# 15fpga.net
KiCad netlist of a schematic drawn in Altium Designer
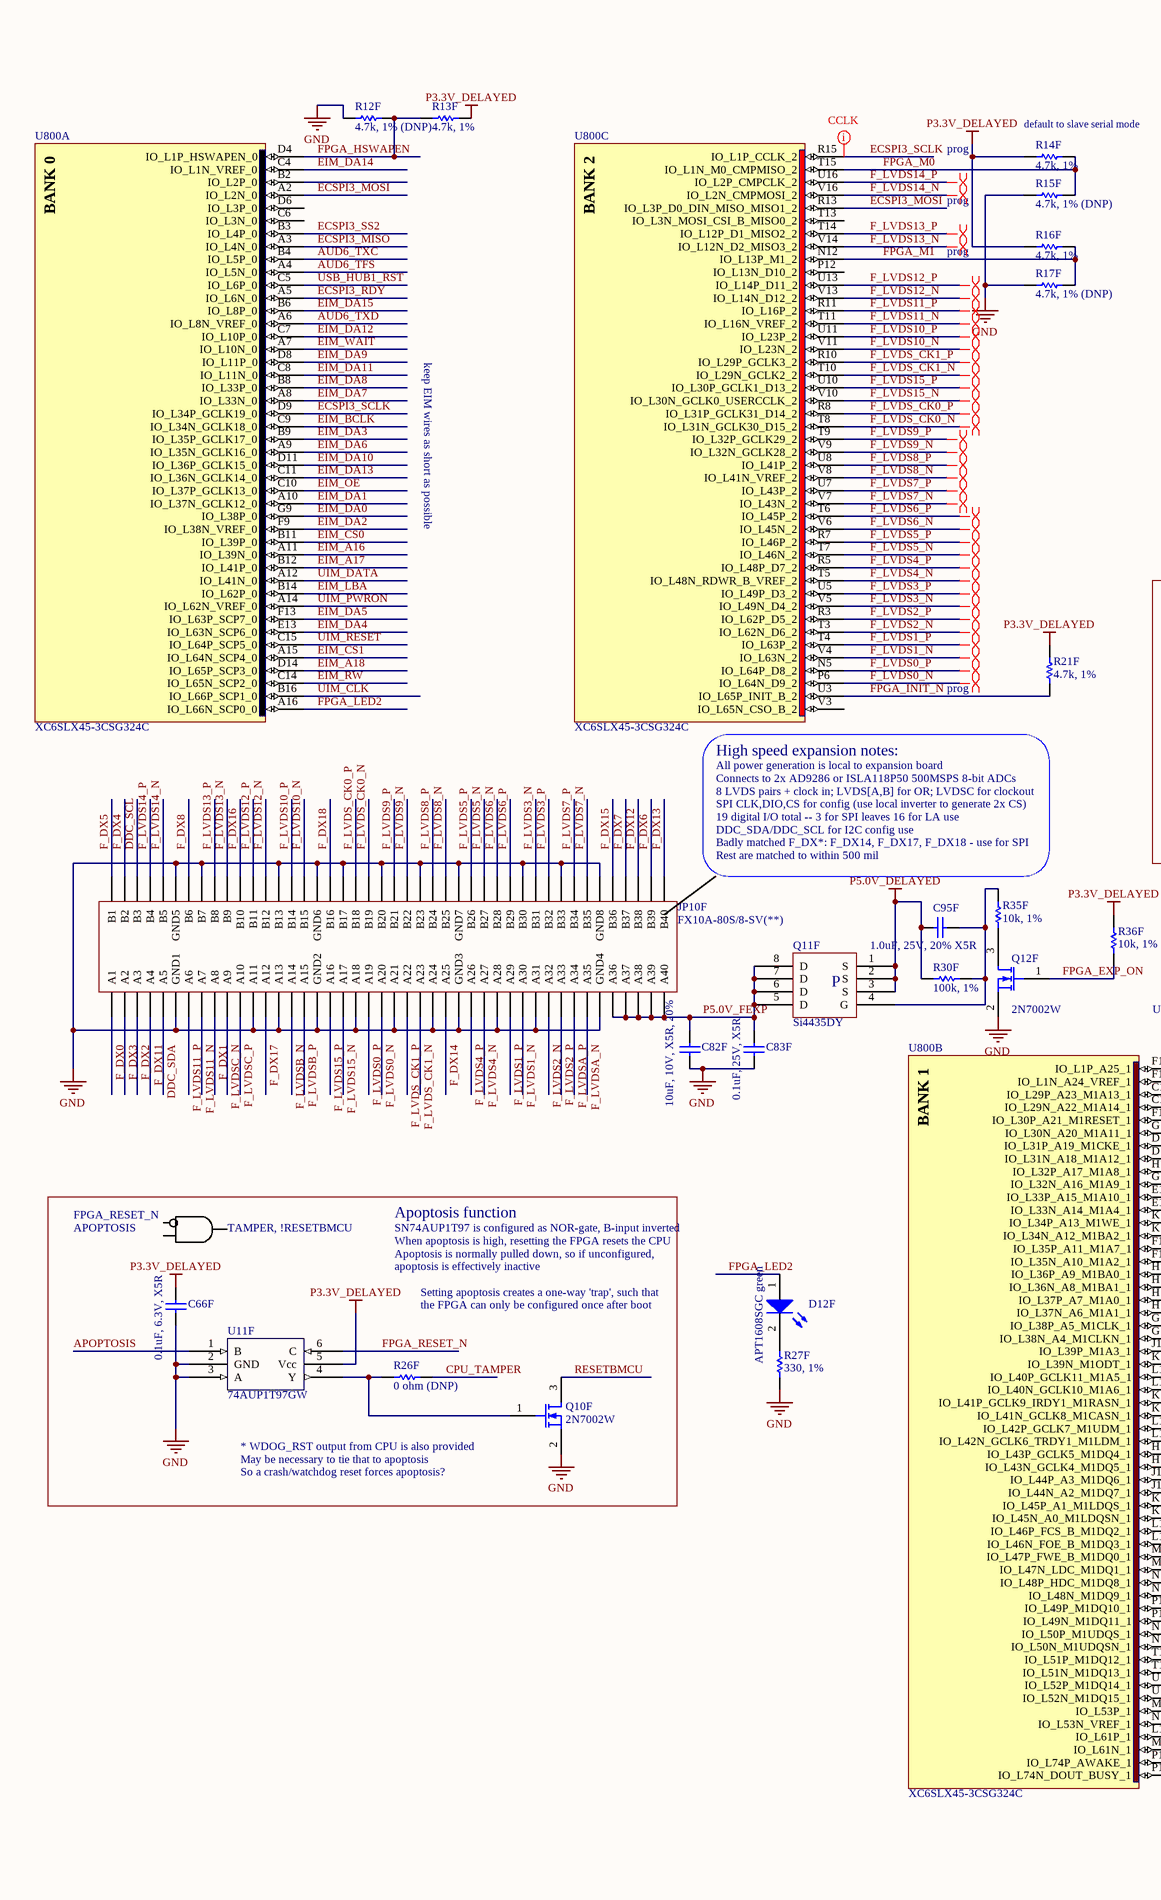
[diagram p0: 15fpga.SchDoc, left]
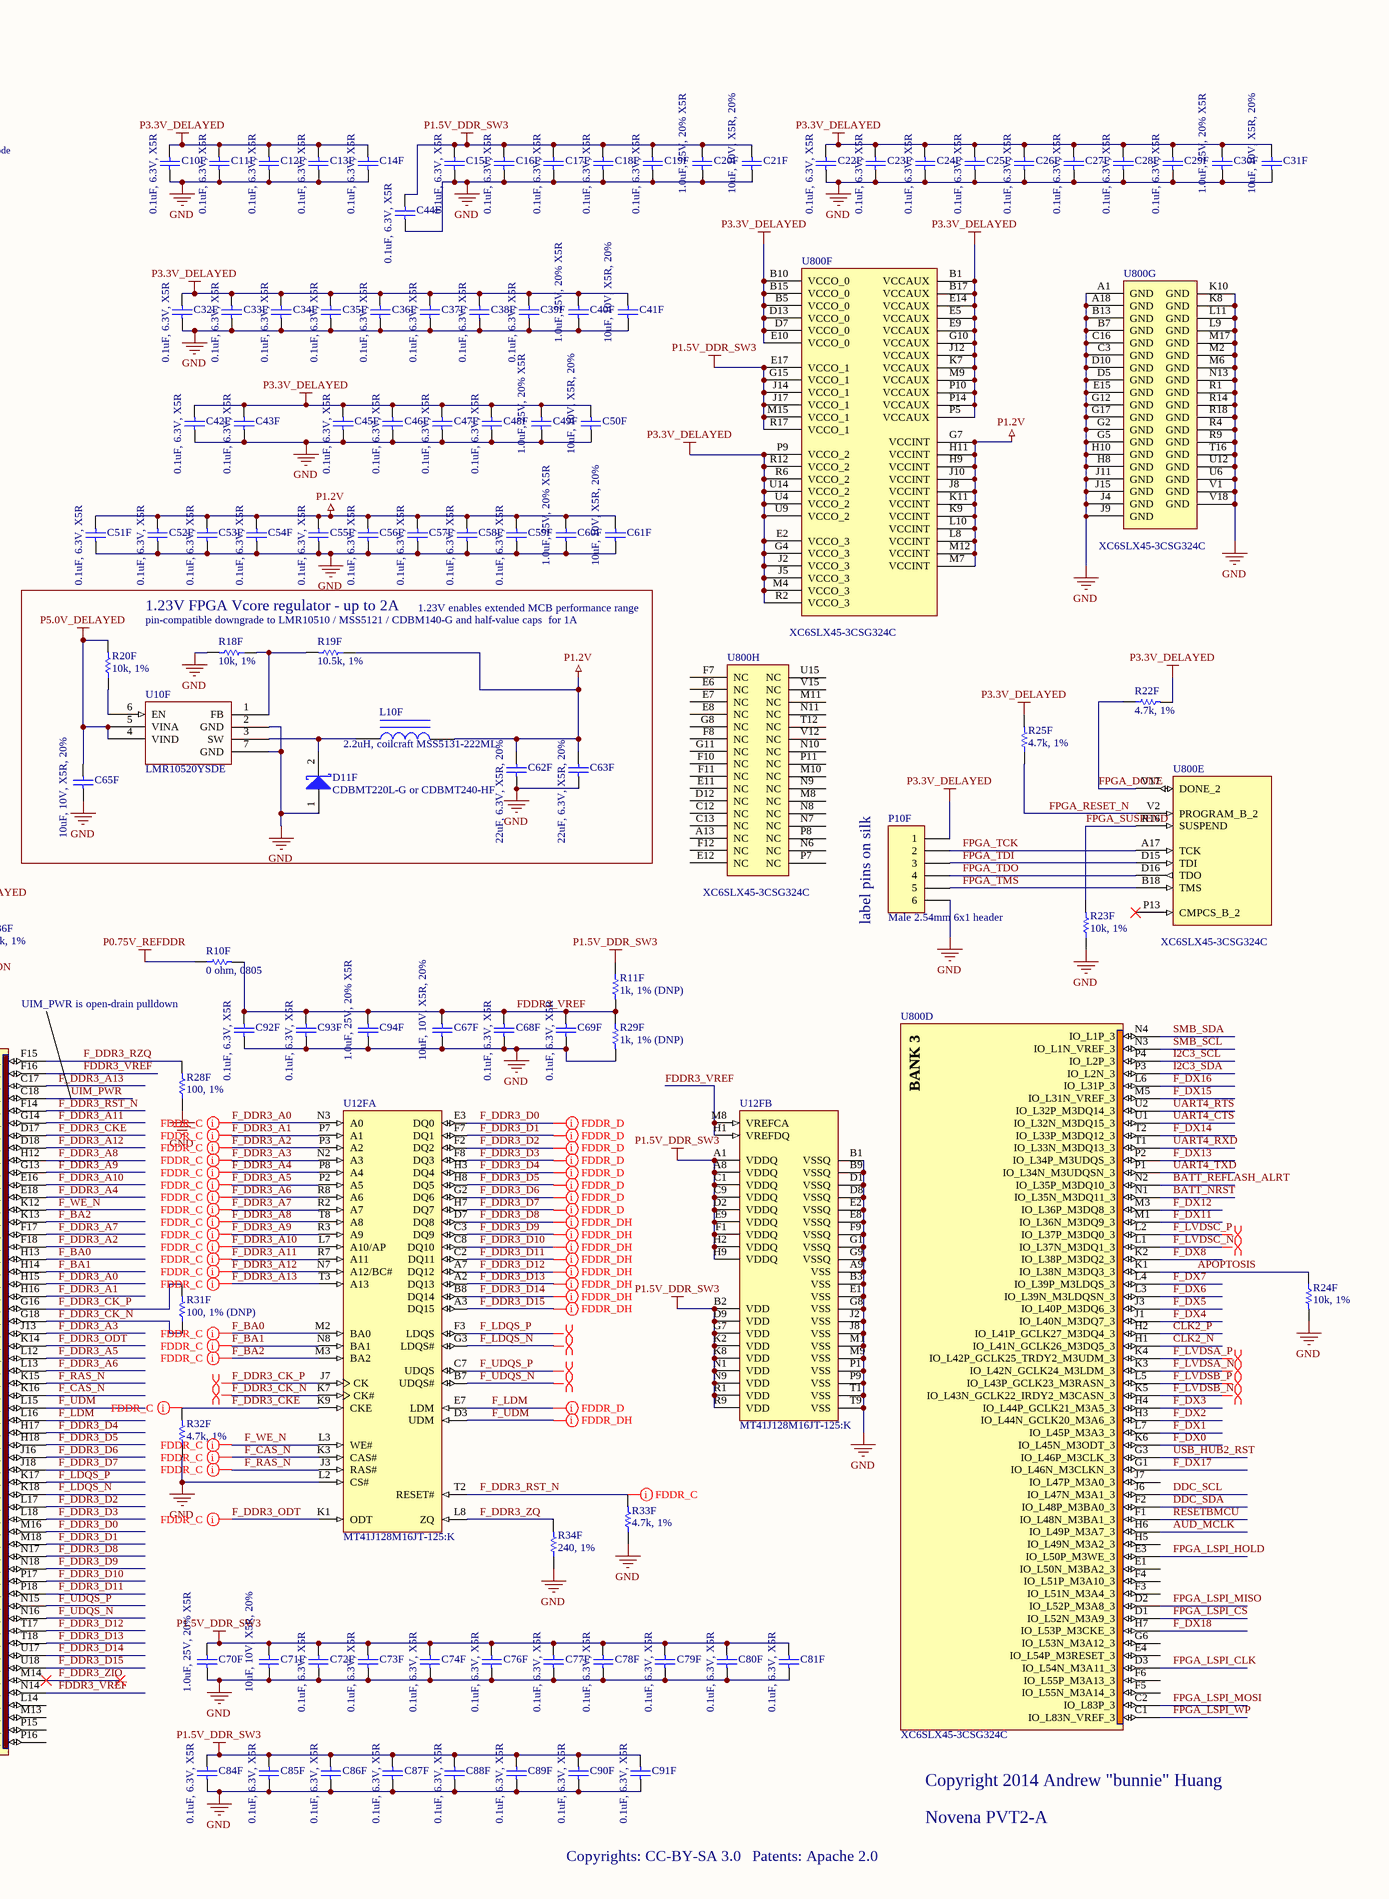
[diagram p1: 15fpga.SchDoc, right]

(export (version "E")
  (design (tool "Eeschema 10.0.6"))
  (components
    (comp (ref "C10F")
      (value "0.1uF, 6.3V, X5R")
      (footprint "CAPC0603N_B")
      (description "Capacitor (Semiconductor SIM Model)")
      (fields (field (name "PUBLISHER") "Altium Limited"))
      (libsource (lib "Miscellaneous Devices") (part "Cap Semi"))
    )
    (comp (ref "C11F")
      (value "0.1uF, 6.3V, X5R")
      (footprint "CAPC0603N_B")
      (description "Capacitor (Semiconductor SIM Model)")
      (fields (field (name "PUBLISHER") "Altium Limited"))
      (libsource (lib "Miscellaneous Devices") (part "Cap Semi"))
    )
    (comp (ref "C12F")
      (value "0.1uF, 6.3V, X5R")
      (footprint "CAPC0603N_B")
      (description "Capacitor (Semiconductor SIM Model)")
      (fields (field (name "PUBLISHER") "Altium Limited"))
      (libsource (lib "Miscellaneous Devices") (part "Cap Semi"))
    )
    (comp (ref "C13F")
      (value "0.1uF, 6.3V, X5R")
      (footprint "CAPC0603N_B")
      (description "Capacitor (Semiconductor SIM Model)")
      (fields (field (name "PUBLISHER") "Altium Limited"))
      (libsource (lib "Miscellaneous Devices") (part "Cap Semi"))
    )
    (comp (ref "C14F")
      (value "0.1uF, 6.3V, X5R")
      (footprint "CAPC0603N_B")
      (description "Capacitor (Semiconductor SIM Model)")
      (fields (field (name "PUBLISHER") "Altium Limited"))
      (libsource (lib "Miscellaneous Devices") (part "Cap Semi"))
    )
    (comp (ref "C15F")
      (value "0.1uF, 6.3V, X5R")
      (footprint "CAPC0603N_B")
      (description "Capacitor (Semiconductor SIM Model)")
      (fields (field (name "PUBLISHER") "Altium Limited"))
      (libsource (lib "Miscellaneous Devices") (part "Cap Semi"))
    )
    (comp (ref "C16F")
      (value "0.1uF, 6.3V, X5R")
      (footprint "CAPC0603N_B")
      (description "Capacitor (Semiconductor SIM Model)")
      (fields (field (name "PUBLISHER") "Altium Limited"))
      (libsource (lib "Miscellaneous Devices") (part "Cap Semi"))
    )
    (comp (ref "C17F")
      (value "0.1uF, 6.3V, X5R")
      (footprint "CAPC0603N_B")
      (description "Capacitor (Semiconductor SIM Model)")
      (fields (field (name "PUBLISHER") "Altium Limited"))
      (libsource (lib "Miscellaneous Devices") (part "Cap Semi"))
    )
    (comp (ref "C18F")
      (value "0.1uF, 6.3V, X5R")
      (footprint "CAPC0603N_B")
      (description "Capacitor (Semiconductor SIM Model)")
      (fields (field (name "PUBLISHER") "Altium Limited"))
      (libsource (lib "Miscellaneous Devices") (part "Cap Semi"))
    )
    (comp (ref "C19F")
      (value "0.1uF, 6.3V, X5R")
      (footprint "CAPC0603N_B")
      (description "Capacitor (Semiconductor SIM Model)")
      (fields (field (name "PUBLISHER") "Altium Limited"))
      (libsource (lib "Miscellaneous Devices") (part "Cap Semi"))
    )
    (comp (ref "C20F")
      (value "1.0uF, 25V, 20% X5R")
      (footprint "CAPC1608N")
      (description "Capacitor (Semiconductor SIM Model)")
      (fields (field (name "PUBLISHER") "Altium Limited"))
      (libsource (lib "Miscellaneous Devices") (part "Cap Semi"))
    )
    (comp (ref "C21F")
      (value "10uF, 10V, X5R, 20%")
      (footprint "CAPC1608N")
      (description "Capacitor (Semiconductor SIM Model)")
      (fields (field (name "PUBLISHER") "Altium Limited"))
      (libsource (lib "Miscellaneous Devices") (part "Cap Semi"))
    )
    (comp (ref "C22F")
      (value "0.1uF, 6.3V, X5R")
      (footprint "CAPC0603N_B")
      (description "Capacitor (Semiconductor SIM Model)")
      (fields (field (name "PUBLISHER") "Altium Limited"))
      (libsource (lib "Miscellaneous Devices") (part "Cap Semi"))
    )
    (comp (ref "C23F")
      (value "0.1uF, 6.3V, X5R")
      (footprint "CAPC0603N_B")
      (description "Capacitor (Semiconductor SIM Model)")
      (fields (field (name "PUBLISHER") "Altium Limited"))
      (libsource (lib "Miscellaneous Devices") (part "Cap Semi"))
    )
    (comp (ref "C24F")
      (value "0.1uF, 6.3V, X5R")
      (footprint "CAPC0603N_B")
      (description "Capacitor (Semiconductor SIM Model)")
      (fields (field (name "PUBLISHER") "Altium Limited"))
      (libsource (lib "Miscellaneous Devices") (part "Cap Semi"))
    )
    (comp (ref "C25F")
      (value "0.1uF, 6.3V, X5R")
      (footprint "CAPC0603N_B")
      (description "Capacitor (Semiconductor SIM Model)")
      (fields (field (name "PUBLISHER") "Altium Limited"))
      (libsource (lib "Miscellaneous Devices") (part "Cap Semi"))
    )
    (comp (ref "C26F")
      (value "0.1uF, 6.3V, X5R")
      (footprint "CAPC0603N_B")
      (description "Capacitor (Semiconductor SIM Model)")
      (fields (field (name "PUBLISHER") "Altium Limited"))
      (libsource (lib "Miscellaneous Devices") (part "Cap Semi"))
    )
    (comp (ref "C27F")
      (value "0.1uF, 6.3V, X5R")
      (footprint "CAPC0603N_B")
      (description "Capacitor (Semiconductor SIM Model)")
      (fields (field (name "PUBLISHER") "Altium Limited"))
      (libsource (lib "Miscellaneous Devices") (part "Cap Semi"))
    )
    (comp (ref "C28F")
      (value "0.1uF, 6.3V, X5R")
      (footprint "CAPC0603N_B")
      (description "Capacitor (Semiconductor SIM Model)")
      (fields (field (name "PUBLISHER") "Altium Limited"))
      (libsource (lib "Miscellaneous Devices") (part "Cap Semi"))
    )
    (comp (ref "C29F")
      (value "0.1uF, 6.3V, X5R")
      (footprint "CAPC0603N_B")
      (description "Capacitor (Semiconductor SIM Model)")
      (fields (field (name "PUBLISHER") "Altium Limited"))
      (libsource (lib "Miscellaneous Devices") (part "Cap Semi"))
    )
    (comp (ref "C30F")
      (value "1.0uF, 25V, 20% X5R")
      (footprint "CAPC1608N")
      (description "Capacitor (Semiconductor SIM Model)")
      (fields (field (name "PUBLISHER") "Altium Limited"))
      (libsource (lib "Miscellaneous Devices") (part "Cap Semi"))
    )
    (comp (ref "C31F")
      (value "10uF, 10V, X5R, 20%")
      (footprint "CAPC1608N")
      (description "Capacitor (Semiconductor SIM Model)")
      (fields (field (name "PUBLISHER") "Altium Limited"))
      (libsource (lib "Miscellaneous Devices") (part "Cap Semi"))
    )
    (comp (ref "C32F")
      (value "0.1uF, 6.3V, X5R")
      (footprint "CAPC0603N_B")
      (description "Capacitor (Semiconductor SIM Model)")
      (fields (field (name "PUBLISHER") "Altium Limited"))
      (libsource (lib "Miscellaneous Devices") (part "Cap Semi"))
    )
    (comp (ref "C33F")
      (value "0.1uF, 6.3V, X5R")
      (footprint "CAPC0603N_B")
      (description "Capacitor (Semiconductor SIM Model)")
      (fields (field (name "PUBLISHER") "Altium Limited"))
      (libsource (lib "Miscellaneous Devices") (part "Cap Semi"))
    )
    (comp (ref "C34F")
      (value "0.1uF, 6.3V, X5R")
      (footprint "CAPC0603N_B")
      (description "Capacitor (Semiconductor SIM Model)")
      (fields (field (name "PUBLISHER") "Altium Limited"))
      (libsource (lib "Miscellaneous Devices") (part "Cap Semi"))
    )
    (comp (ref "C35F")
      (value "0.1uF, 6.3V, X5R")
      (footprint "CAPC0603N_B")
      (description "Capacitor (Semiconductor SIM Model)")
      (fields (field (name "PUBLISHER") "Altium Limited"))
      (libsource (lib "Miscellaneous Devices") (part "Cap Semi"))
    )
    (comp (ref "C36F")
      (value "0.1uF, 6.3V, X5R")
      (footprint "CAPC0603N_B")
      (description "Capacitor (Semiconductor SIM Model)")
      (fields (field (name "PUBLISHER") "Altium Limited"))
      (libsource (lib "Miscellaneous Devices") (part "Cap Semi"))
    )
    (comp (ref "C37F")
      (value "0.1uF, 6.3V, X5R")
      (footprint "CAPC0603N_B")
      (description "Capacitor (Semiconductor SIM Model)")
      (fields (field (name "PUBLISHER") "Altium Limited"))
      (libsource (lib "Miscellaneous Devices") (part "Cap Semi"))
    )
    (comp (ref "C38F")
      (value "0.1uF, 6.3V, X5R")
      (footprint "CAPC0603N_B")
      (description "Capacitor (Semiconductor SIM Model)")
      (fields (field (name "PUBLISHER") "Altium Limited"))
      (libsource (lib "Miscellaneous Devices") (part "Cap Semi"))
    )
    (comp (ref "C39F")
      (value "0.1uF, 6.3V, X5R")
      (footprint "CAPC0603N_B")
      (description "Capacitor (Semiconductor SIM Model)")
      (fields (field (name "PUBLISHER") "Altium Limited"))
      (libsource (lib "Miscellaneous Devices") (part "Cap Semi"))
    )
    (comp (ref "C40F")
      (value "1.0uF, 25V, 20% X5R")
      (footprint "CAPC1608N")
      (description "Capacitor (Semiconductor SIM Model)")
      (fields (field (name "PUBLISHER") "Altium Limited"))
      (libsource (lib "Miscellaneous Devices") (part "Cap Semi"))
    )
    (comp (ref "C41F")
      (value "10uF, 10V, X5R, 20%")
      (footprint "CAPC1608N")
      (description "Capacitor (Semiconductor SIM Model)")
      (fields (field (name "PUBLISHER") "Altium Limited"))
      (libsource (lib "Miscellaneous Devices") (part "Cap Semi"))
    )
    (comp (ref "C42F")
      (value "0.1uF, 6.3V, X5R")
      (footprint "CAPC0603N_B")
      (description "Capacitor (Semiconductor SIM Model)")
      (fields (field (name "PUBLISHER") "Altium Limited"))
      (libsource (lib "Miscellaneous Devices") (part "Cap Semi"))
    )
    (comp (ref "C43F")
      (value "0.1uF, 6.3V, X5R")
      (footprint "CAPC0603N_B")
      (description "Capacitor (Semiconductor SIM Model)")
      (fields (field (name "PUBLISHER") "Altium Limited"))
      (libsource (lib "Miscellaneous Devices") (part "Cap Semi"))
    )
    (comp (ref "C44F")
      (value "0.1uF, 6.3V, X5R")
      (footprint "CAPC0603N_B")
      (description "Capacitor (Semiconductor SIM Model)")
      (fields (field (name "PUBLISHER") "Altium Limited"))
      (libsource (lib "Miscellaneous Devices") (part "Cap Semi"))
    )
    (comp (ref "C45F")
      (value "0.1uF, 6.3V, X5R")
      (footprint "CAPC0603N_B")
      (description "Capacitor (Semiconductor SIM Model)")
      (fields (field (name "PUBLISHER") "Altium Limited"))
      (libsource (lib "Miscellaneous Devices") (part "Cap Semi"))
    )
    (comp (ref "C46F")
      (value "0.1uF, 6.3V, X5R")
      (footprint "CAPC0603N_B")
      (description "Capacitor (Semiconductor SIM Model)")
      (fields (field (name "PUBLISHER") "Altium Limited"))
      (libsource (lib "Miscellaneous Devices") (part "Cap Semi"))
    )
    (comp (ref "C47F")
      (value "0.1uF, 6.3V, X5R")
      (footprint "CAPC0603N_B")
      (description "Capacitor (Semiconductor SIM Model)")
      (fields (field (name "PUBLISHER") "Altium Limited"))
      (libsource (lib "Miscellaneous Devices") (part "Cap Semi"))
    )
    (comp (ref "C48F")
      (value "0.1uF, 6.3V, X5R")
      (footprint "CAPC0603N_B")
      (description "Capacitor (Semiconductor SIM Model)")
      (fields (field (name "PUBLISHER") "Altium Limited"))
      (libsource (lib "Miscellaneous Devices") (part "Cap Semi"))
    )
    (comp (ref "C49F")
      (value "1.0uF, 25V, 20% X5R")
      (footprint "CAPC1608N")
      (description "Capacitor (Semiconductor SIM Model)")
      (fields (field (name "PUBLISHER") "Altium Limited"))
      (libsource (lib "Miscellaneous Devices") (part "Cap Semi"))
    )
    (comp (ref "C50F")
      (value "10uF, 10V, X5R, 20%")
      (footprint "CAPC1608N")
      (description "Capacitor (Semiconductor SIM Model)")
      (fields (field (name "PUBLISHER") "Altium Limited"))
      (libsource (lib "Miscellaneous Devices") (part "Cap Semi"))
    )
    (comp (ref "C51F")
      (value "0.1uF, 6.3V, X5R")
      (footprint "CAPC0603N_B")
      (description "Capacitor (Semiconductor SIM Model)")
      (fields (field (name "PUBLISHER") "Altium Limited"))
      (libsource (lib "Miscellaneous Devices") (part "Cap Semi"))
    )
    (comp (ref "C52F")
      (value "0.1uF, 6.3V, X5R")
      (footprint "CAPC0603N_B")
      (description "Capacitor (Semiconductor SIM Model)")
      (fields (field (name "PUBLISHER") "Altium Limited"))
      (libsource (lib "Miscellaneous Devices") (part "Cap Semi"))
    )
    (comp (ref "C53F")
      (value "0.1uF, 6.3V, X5R")
      (footprint "CAPC0603N_B")
      (description "Capacitor (Semiconductor SIM Model)")
      (fields (field (name "PUBLISHER") "Altium Limited"))
      (libsource (lib "Miscellaneous Devices") (part "Cap Semi"))
    )
    (comp (ref "C54F")
      (value "0.1uF, 6.3V, X5R")
      (footprint "CAPC0603N_B")
      (description "Capacitor (Semiconductor SIM Model)")
      (fields (field (name "PUBLISHER") "Altium Limited"))
      (libsource (lib "Miscellaneous Devices") (part "Cap Semi"))
    )
    (comp (ref "C55F")
      (value "0.1uF, 6.3V, X5R")
      (footprint "CAPC0603N_B")
      (description "Capacitor (Semiconductor SIM Model)")
      (fields (field (name "PUBLISHER") "Altium Limited"))
      (libsource (lib "Miscellaneous Devices") (part "Cap Semi"))
    )
    (comp (ref "C56F")
      (value "0.1uF, 6.3V, X5R")
      (footprint "CAPC0603N_B")
      (description "Capacitor (Semiconductor SIM Model)")
      (fields (field (name "PUBLISHER") "Altium Limited"))
      (libsource (lib "Miscellaneous Devices") (part "Cap Semi"))
    )
    (comp (ref "C57F")
      (value "0.1uF, 6.3V, X5R")
      (footprint "CAPC0603N_B")
      (description "Capacitor (Semiconductor SIM Model)")
      (fields (field (name "PUBLISHER") "Altium Limited"))
      (libsource (lib "Miscellaneous Devices") (part "Cap Semi"))
    )
    (comp (ref "C58F")
      (value "0.1uF, 6.3V, X5R")
      (footprint "CAPC0603N_B")
      (description "Capacitor (Semiconductor SIM Model)")
      (fields (field (name "PUBLISHER") "Altium Limited"))
      (libsource (lib "Miscellaneous Devices") (part "Cap Semi"))
    )
    (comp (ref "C59F")
      (value "0.1uF, 6.3V, X5R")
      (footprint "CAPC0603N_B")
      (description "Capacitor (Semiconductor SIM Model)")
      (fields (field (name "PUBLISHER") "Altium Limited"))
      (libsource (lib "Miscellaneous Devices") (part "Cap Semi"))
    )
    (comp (ref "C60F")
      (value "1.0uF, 25V, 20% X5R")
      (footprint "CAPC1608N")
      (description "Capacitor (Semiconductor SIM Model)")
      (fields (field (name "PUBLISHER") "Altium Limited"))
      (libsource (lib "Miscellaneous Devices") (part "Cap Semi"))
    )
    (comp (ref "C61F")
      (value "10uF, 10V, X5R, 20%")
      (footprint "CAPC1608N")
      (description "Capacitor (Semiconductor SIM Model)")
      (fields (field (name "PUBLISHER") "Altium Limited"))
      (libsource (lib "Miscellaneous Devices") (part "Cap Semi"))
    )
    (comp (ref "C62F")
      (value "22uF, 6.3V, X5R, 20%")
      (footprint "CAPC1608N_HD")
      (description "Capacitor (Semiconductor SIM Model)")
      (fields (field (name "PUBLISHER") "Altium Limited"))
      (libsource (lib "Miscellaneous Devices") (part "Cap Semi"))
    )
    (comp (ref "C63F")
      (value "22uF, 6.3V, X5R, 20%")
      (footprint "CAPC1608N_HD")
      (description "Capacitor (Semiconductor SIM Model)")
      (fields (field (name "PUBLISHER") "Altium Limited"))
      (libsource (lib "Miscellaneous Devices") (part "Cap Semi"))
    )
    (comp (ref "C65F")
      (value "10uF, 10V, X5R, 20%")
      (footprint "CAPC1608N")
      (description "Capacitor (Semiconductor SIM Model)")
      (fields (field (name "PUBLISHER") "Altium Limited"))
      (libsource (lib "Miscellaneous Devices") (part "Cap Semi"))
    )
    (comp (ref "C66F")
      (value "0.1uF, 6.3V, X5R")
      (footprint "CAPC0603N_B")
      (description "Capacitor (Semiconductor SIM Model)")
      (fields (field (name "PUBLISHER") "Altium Limited"))
      (libsource (lib "Miscellaneous Devices") (part "Cap Semi"))
    )
    (comp (ref "C67F")
      (value "10uF, 10V, X5R, 20%")
      (footprint "CAPC1608N")
      (description "Capacitor (Semiconductor SIM Model)")
      (fields (field (name "PUBLISHER") "Altium Limited"))
      (libsource (lib "Miscellaneous Devices") (part "Cap Semi"))
    )
    (comp (ref "C68F")
      (value "0.1uF, 6.3V, X5R")
      (footprint "CAPC0603N_B")
      (description "Capacitor (Semiconductor SIM Model)")
      (fields (field (name "PUBLISHER") "Altium Limited"))
      (libsource (lib "Miscellaneous Devices") (part "Cap Semi"))
    )
    (comp (ref "C69F")
      (value "0.1uF, 6.3V, X5R")
      (footprint "CAPC0603N_B")
      (description "Capacitor (Semiconductor SIM Model)")
      (fields (field (name "PUBLISHER") "Altium Limited"))
      (libsource (lib "Miscellaneous Devices") (part "Cap Semi"))
    )
    (comp (ref "C70F")
      (value "1.0uF, 25V, 20% X5R")
      (footprint "CAPC1608N")
      (description "Capacitor (Semiconductor SIM Model)")
      (fields (field (name "PUBLISHER") "Altium Limited"))
      (libsource (lib "Miscellaneous Devices") (part "Cap Semi"))
    )
    (comp (ref "C71F")
      (value "10uF, 10V, X5R, 20%")
      (footprint "CAPC1608N")
      (description "Capacitor (Semiconductor SIM Model)")
      (fields (field (name "PUBLISHER") "Altium Limited"))
      (libsource (lib "Miscellaneous Devices") (part "Cap Semi"))
    )
    (comp (ref "C72F")
      (value "0.1uF, 6.3V, X5R")
      (footprint "CAPC0603N_B")
      (description "Capacitor (Semiconductor SIM Model)")
      (fields (field (name "PUBLISHER") "Altium Limited"))
      (libsource (lib "Miscellaneous Devices") (part "Cap Semi"))
    )
    (comp (ref "C73F")
      (value "0.1uF, 6.3V, X5R")
      (footprint "CAPC0603N_B")
      (description "Capacitor (Semiconductor SIM Model)")
      (fields (field (name "PUBLISHER") "Altium Limited"))
      (libsource (lib "Miscellaneous Devices") (part "Cap Semi"))
    )
    (comp (ref "C74F")
      (value "0.1uF, 6.3V, X5R")
      (footprint "CAPC0603N_B")
      (description "Capacitor (Semiconductor SIM Model)")
      (fields (field (name "PUBLISHER") "Altium Limited"))
      (libsource (lib "Miscellaneous Devices") (part "Cap Semi"))
    )
    (comp (ref "C76F")
      (value "0.1uF, 6.3V, X5R")
      (footprint "CAPC0603N_B")
      (description "Capacitor (Semiconductor SIM Model)")
      (fields (field (name "PUBLISHER") "Altium Limited"))
      (libsource (lib "Miscellaneous Devices") (part "Cap Semi"))
    )
    (comp (ref "C77F")
      (value "0.1uF, 6.3V, X5R")
      (footprint "CAPC0603N_B")
      (description "Capacitor (Semiconductor SIM Model)")
      (fields (field (name "PUBLISHER") "Altium Limited"))
      (libsource (lib "Miscellaneous Devices") (part "Cap Semi"))
    )
    (comp (ref "C78F")
      (value "0.1uF, 6.3V, X5R")
      (footprint "CAPC0603N_B")
      (description "Capacitor (Semiconductor SIM Model)")
      (fields (field (name "PUBLISHER") "Altium Limited"))
      (libsource (lib "Miscellaneous Devices") (part "Cap Semi"))
    )
    (comp (ref "C79F")
      (value "0.1uF, 6.3V, X5R")
      (footprint "CAPC0603N_B")
      (description "Capacitor (Semiconductor SIM Model)")
      (fields (field (name "PUBLISHER") "Altium Limited"))
      (libsource (lib "Miscellaneous Devices") (part "Cap Semi"))
    )
    (comp (ref "C80F")
      (value "0.1uF, 6.3V, X5R")
      (footprint "CAPC0603N_B")
      (description "Capacitor (Semiconductor SIM Model)")
      (fields (field (name "PUBLISHER") "Altium Limited"))
      (libsource (lib "Miscellaneous Devices") (part "Cap Semi"))
    )
    (comp (ref "C81F")
      (value "0.1uF, 6.3V, X5R")
      (footprint "CAPC0603N_B")
      (description "Capacitor (Semiconductor SIM Model)")
      (fields (field (name "PUBLISHER") "Altium Limited"))
      (libsource (lib "Miscellaneous Devices") (part "Cap Semi"))
    )
    (comp (ref "C82F")
      (value "10uF, 10V, X5R, 20%")
      (footprint "CAPC1608N")
      (description "Capacitor (Semiconductor SIM Model)")
      (fields (field (name "PUBLISHER") "Altium Limited"))
      (libsource (lib "Miscellaneous Devices") (part "Cap Semi"))
    )
    (comp (ref "C83F")
      (value "0.1uF, 25V, X5R")
      (footprint "CAPC1005N")
      (description "Capacitor (Semiconductor SIM Model)")
      (fields (field (name "PUBLISHER") "Altium Limited"))
      (libsource (lib "Miscellaneous Devices") (part "Cap Semi"))
    )
    (comp (ref "C84F")
      (value "0.1uF, 6.3V, X5R")
      (footprint "CAPC0603N_B")
      (description "Capacitor (Semiconductor SIM Model)")
      (fields (field (name "PUBLISHER") "Altium Limited"))
      (libsource (lib "Miscellaneous Devices") (part "Cap Semi"))
    )
    (comp (ref "C85F")
      (value "0.1uF, 6.3V, X5R")
      (footprint "CAPC0603N_B")
      (description "Capacitor (Semiconductor SIM Model)")
      (fields (field (name "PUBLISHER") "Altium Limited"))
      (libsource (lib "Miscellaneous Devices") (part "Cap Semi"))
    )
    (comp (ref "C86F")
      (value "0.1uF, 6.3V, X5R")
      (footprint "CAPC0603N_B")
      (description "Capacitor (Semiconductor SIM Model)")
      (fields (field (name "PUBLISHER") "Altium Limited"))
      (libsource (lib "Miscellaneous Devices") (part "Cap Semi"))
    )
    (comp (ref "C87F")
      (value "0.1uF, 6.3V, X5R")
      (footprint "CAPC0603N_B")
      (description "Capacitor (Semiconductor SIM Model)")
      (fields (field (name "PUBLISHER") "Altium Limited"))
      (libsource (lib "Miscellaneous Devices") (part "Cap Semi"))
    )
    (comp (ref "C88F")
      (value "0.1uF, 6.3V, X5R")
      (footprint "CAPC0603N_B")
      (description "Capacitor (Semiconductor SIM Model)")
      (fields (field (name "PUBLISHER") "Altium Limited"))
      (libsource (lib "Miscellaneous Devices") (part "Cap Semi"))
    )
    (comp (ref "C89F")
      (value "0.1uF, 6.3V, X5R")
      (footprint "CAPC0603N_B")
      (description "Capacitor (Semiconductor SIM Model)")
      (fields (field (name "PUBLISHER") "Altium Limited"))
      (libsource (lib "Miscellaneous Devices") (part "Cap Semi"))
    )
    (comp (ref "C90F")
      (value "0.1uF, 6.3V, X5R")
      (footprint "CAPC0603N_B")
      (description "Capacitor (Semiconductor SIM Model)")
      (fields (field (name "PUBLISHER") "Altium Limited"))
      (libsource (lib "Miscellaneous Devices") (part "Cap Semi"))
    )
    (comp (ref "C91F")
      (value "0.1uF, 6.3V, X5R")
      (footprint "CAPC0603N_B")
      (description "Capacitor (Semiconductor SIM Model)")
      (fields (field (name "PUBLISHER") "Altium Limited"))
      (libsource (lib "Miscellaneous Devices") (part "Cap Semi"))
    )
    (comp (ref "C92F")
      (value "0.1uF, 6.3V, X5R")
      (footprint "CAPC0603N_B")
      (description "Capacitor (Semiconductor SIM Model)")
      (fields (field (name "PUBLISHER") "Altium Limited"))
      (libsource (lib "Miscellaneous Devices") (part "Cap Semi"))
    )
    (comp (ref "C93F")
      (value "0.1uF, 6.3V, X5R")
      (footprint "CAPC0603N_B")
      (description "Capacitor (Semiconductor SIM Model)")
      (fields (field (name "PUBLISHER") "Altium Limited"))
      (libsource (lib "Miscellaneous Devices") (part "Cap Semi"))
    )
    (comp (ref "C94F")
      (value "1.0uF, 25V, 20% X5R")
      (footprint "CAPC1608N")
      (description "Capacitor (Semiconductor SIM Model)")
      (fields (field (name "PUBLISHER") "Altium Limited"))
      (libsource (lib "Miscellaneous Devices") (part "Cap Semi"))
    )
    (comp (ref "C95F")
      (value "1.0uF, 25V, 20% X5R")
      (footprint "CAPC1608N")
      (description "Capacitor (Semiconductor SIM Model)")
      (fields (field (name "PUBLISHER") "Altium Limited"))
      (libsource (lib "Miscellaneous Devices") (part "Cap Semi"))
    )
    (comp (ref "D11F")
      (value "CDBMT220L-G or CDBMT240-HF")
      (footprint "SOD123")
      (description "Schottky Diode")
      (fields (field (name "PUBLISHER") "Altium Limited"))
      (libsource (lib "Miscellaneous Devices") (part "D Schottky"))
    )
    (comp (ref "D12F")
      (value "APT1608SGC green")
      (footprint "CD1608-0603")
      (description "Typical RED, GREEN, YELLOW, AMBER GaAs LED")
      (fields (field (name "PUBLISHER") "Altium Limited"))
      (libsource (lib "Miscellaneous Devices") (part "LED2"))
    )
    (comp (ref "JP10F")
      (value "FX10A-80S/8-SV(**)")
      (footprint "HRS_FX10A-80S/8-SV1(**)")
      (description "80-pin 10Gbps 5mm mated height board-to-board connector")
      (libsource (lib "commonsch") (part "HEADER_HRS_FX10A_80"))
    )
    (comp (ref "L10F")
      (value "2.2uH, coilcraft MSS5131-222ML")
      (footprint "COILCRAFT_MSS5121")
      (description "Magnetic-Core Inductor")
      (fields (field (name "PUBLISHER") "Altium Limited"))
      (libsource (lib "Miscellaneous Devices") (part "Inductor Iron"))
    )
    (comp (ref "P10F")
      (value "Male 2.54mm 6x1 header")
      (footprint "HDR1X6")
      (description "Header, 6-Pin")
      (fields (field (name "PUBLISHER") "Altium Limited"))
      (libsource (lib "Miscellaneous Connectors") (part "Header 6"))
    )
    (comp (ref "Q10F")
      (value "2N7002W")
      (footprint "SOT323-3AN")
      (description "N-Channel MOSFET")
      (fields (field (name "PUBLISHER") "Altium Limited"))
      (libsource (lib "Miscellaneous Devices") (part "MOSFET-N"))
    )
    (comp (ref "Q11F")
      (value "Si4435DY")
      (footprint "SOIC127P600-8AN")
      (description "Singre P-channel FET, 8A, 30V")
      (libsource (lib "commonsch") (part "Si4435DY"))
    )
    (comp (ref "Q12F")
      (value "2N7002W")
      (footprint "SOT323-3AN")
      (description "N-Channel MOSFET")
      (fields (field (name "PUBLISHER") "Altium Limited"))
      (libsource (lib "Miscellaneous Devices") (part "MOSFET-N"))
    )
    (comp (ref "R10F")
      (value "0 ohm, 0805")
      (footprint "RESC2012N")
      (description "Resistor")
      (fields (field (name "PUBLISHER") "Altium Limited"))
      (libsource (lib "Miscellaneous Devices") (part "Res1"))
    )
    (comp (ref "R11F")
      (value "1k, 1% (DNP)")
      (footprint "RESC1005N")
      (description "Resistor")
      (fields (field (name "PUBLISHER") "Altium Limited"))
      (libsource (lib "Miscellaneous Devices") (part "Res1"))
    )
    (comp (ref "R12F")
      (value "4.7k, 1% (DNP)")
      (footprint "RESC1005N")
      (description "Resistor")
      (fields (field (name "PUBLISHER") "Altium Limited"))
      (libsource (lib "Miscellaneous Devices") (part "Res1"))
    )
    (comp (ref "R13F")
      (value "4.7k, 1%")
      (footprint "RESC1005N")
      (description "Resistor")
      (fields (field (name "PUBLISHER") "Altium Limited"))
      (libsource (lib "Miscellaneous Devices") (part "Res1"))
    )
    (comp (ref "R14F")
      (value "4.7k, 1%")
      (footprint "RESC1005N")
      (description "Resistor")
      (fields (field (name "PUBLISHER") "Altium Limited"))
      (libsource (lib "Miscellaneous Devices") (part "Res1"))
    )
    (comp (ref "R15F")
      (value "4.7k, 1% (DNP)")
      (footprint "RESC1005N")
      (description "Resistor")
      (fields (field (name "PUBLISHER") "Altium Limited"))
      (libsource (lib "Miscellaneous Devices") (part "Res1"))
    )
    (comp (ref "R16F")
      (value "4.7k, 1%")
      (footprint "RESC1005N")
      (description "Resistor")
      (fields (field (name "PUBLISHER") "Altium Limited"))
      (libsource (lib "Miscellaneous Devices") (part "Res1"))
    )
    (comp (ref "R17F")
      (value "4.7k, 1% (DNP)")
      (footprint "RESC1005N")
      (description "Resistor")
      (fields (field (name "PUBLISHER") "Altium Limited"))
      (libsource (lib "Miscellaneous Devices") (part "Res1"))
    )
    (comp (ref "R18F")
      (value "10k, 1%")
      (footprint "RESC1005N")
      (description "Resistor")
      (fields (field (name "PUBLISHER") "Altium Limited"))
      (libsource (lib "Miscellaneous Devices") (part "Res1"))
    )
    (comp (ref "R19F")
      (value "10.5k, 1%")
      (footprint "RESC1005N")
      (description "Resistor")
      (fields (field (name "PUBLISHER") "Altium Limited"))
      (libsource (lib "Miscellaneous Devices") (part "Res1"))
    )
    (comp (ref "R20F")
      (value "10k, 1%")
      (footprint "RESC1005N")
      (description "Resistor")
      (fields (field (name "PUBLISHER") "Altium Limited"))
      (libsource (lib "Miscellaneous Devices") (part "Res1"))
    )
    (comp (ref "R21F")
      (value "4.7k, 1%")
      (footprint "RESC1005N")
      (description "Resistor")
      (fields (field (name "PUBLISHER") "Altium Limited"))
      (libsource (lib "Miscellaneous Devices") (part "Res1"))
    )
    (comp (ref "R22F")
      (value "4.7k, 1%")
      (footprint "RESC1005N")
      (description "Resistor")
      (fields (field (name "PUBLISHER") "Altium Limited"))
      (libsource (lib "Miscellaneous Devices") (part "Res1"))
    )
    (comp (ref "R23F")
      (value "10k, 1%")
      (footprint "RESC1005N")
      (description "Resistor")
      (fields (field (name "PUBLISHER") "Altium Limited"))
      (libsource (lib "Miscellaneous Devices") (part "Res1"))
    )
    (comp (ref "R24F")
      (value "10k, 1%")
      (footprint "RESC1005N")
      (description "Resistor")
      (fields (field (name "PUBLISHER") "Altium Limited"))
      (libsource (lib "Miscellaneous Devices") (part "Res1"))
    )
    (comp (ref "R25F")
      (value "4.7k, 1%")
      (footprint "RESC1005N")
      (description "Resistor")
      (fields (field (name "PUBLISHER") "Altium Limited"))
      (libsource (lib "Miscellaneous Devices") (part "Res1"))
    )
    (comp (ref "R26F")
      (value "0 ohm (DNP)")
      (footprint "RESC1005N")
      (description "Resistor")
      (fields (field (name "PUBLISHER") "Altium Limited"))
      (libsource (lib "Miscellaneous Devices") (part "Res1"))
    )
    (comp (ref "R27F")
      (value "330, 1%")
      (footprint "RESC1005N")
      (description "Resistor")
      (fields (field (name "PUBLISHER") "Altium Limited"))
      (libsource (lib "Miscellaneous Devices") (part "Res1"))
    )
    (comp (ref "R28F")
      (value "100, 1%")
      (footprint "RESC1005N")
      (description "Resistor")
      (fields (field (name "PUBLISHER") "Altium Limited"))
      (libsource (lib "Miscellaneous Devices") (part "Res1"))
    )
    (comp (ref "R29F")
      (value "1k, 1% (DNP)")
      (footprint "RESC1005N")
      (description "Resistor")
      (fields (field (name "PUBLISHER") "Altium Limited"))
      (libsource (lib "Miscellaneous Devices") (part "Res1"))
    )
    (comp (ref "R30F")
      (value "100k, 1%")
      (footprint "RESC1005N")
      (description "Resistor")
      (fields (field (name "PUBLISHER") "Altium Limited"))
      (libsource (lib "Miscellaneous Devices") (part "Res1"))
    )
    (comp (ref "R31F")
      (value "100, 1% (DNP)")
      (footprint "RESC1005N")
      (description "Resistor")
      (fields (field (name "PUBLISHER") "Altium Limited"))
      (libsource (lib "Miscellaneous Devices") (part "Res1"))
    )
    (comp (ref "R32F")
      (value "4.7k, 1%")
      (footprint "RESC1005N")
      (description "Resistor")
      (fields (field (name "PUBLISHER") "Altium Limited"))
      (libsource (lib "Miscellaneous Devices") (part "Res1"))
    )
    (comp (ref "R33F")
      (value "4.7k, 1%")
      (footprint "RESC1005N")
      (description "Resistor")
      (fields (field (name "PUBLISHER") "Altium Limited"))
      (libsource (lib "Miscellaneous Devices") (part "Res1"))
    )
    (comp (ref "R34F")
      (value "240, 1%")
      (footprint "RESC1005N")
      (description "Resistor")
      (fields (field (name "PUBLISHER") "Altium Limited"))
      (libsource (lib "Miscellaneous Devices") (part "Res1"))
    )
    (comp (ref "R35F")
      (value "10k, 1%")
      (footprint "RESC1005N")
      (description "Resistor")
      (fields (field (name "PUBLISHER") "Altium Limited"))
      (libsource (lib "Miscellaneous Devices") (part "Res1"))
    )
    (comp (ref "R36F")
      (value "10k, 1%")
      (footprint "RESC1005N")
      (description "Resistor")
      (fields (field (name "PUBLISHER") "Altium Limited"))
      (libsource (lib "Miscellaneous Devices") (part "Res1"))
    )
    (comp (ref "U10F")
      (value "LMR10520YSDE")
      (footprint "SON95P300X300X80-7V")
      (description "NatSemi 1.5A step-down regulator in LLP")
      (libsource (lib "commonsch") (part "LMR10515XSD"))
    )
    (comp (ref "U11F")
      (value "74AUP1T97GW")
      (footprint "SOT363-6N")
      (description "Single-supply voltage translator, multiple logic function")
      (libsource (lib "*") (part "SN74AUP1T98DBV"))
    )
    (comp (ref "U12F")
      (value "MT41J128M16JT-125:K")
      (footprint "MICT-HA-96")
      (description "2Gb DDR3-1600 SDRAM, 128Mb x 16, 1.25ns, 1.5V, 0 to 95 degC, 96-Ball FBGA, Pb-Free")
      (fields (field (name "VOLTAGE") "1.5V ") (field (name "MANUFACTURER") "Micron"))
      (libsource (lib "Micron Memory DDR3 SDRAM") (part "MT41J128M16HA-125"))
    )
    (comp (ref "U800")
      (value "XC6SLX45-3CSG324C")
      (footprint "CSG324")
      (fields (field (name "PUBLISHER") "Altium Limited"))
      (libsource (lib "Xilinx Spartan-6") (part "XC6SLX9-2CSG324C"))
    )
  )
  (nets
    (net (code "1") (name "/APOPTOSIS") (class "Default")
      (node (ref "R24F") (pin "1") (pinfunction "1_1") (pintype "passive"))
      (node (ref "U11F") (pin "1") (pinfunction "B_1") (pintype "input"))
      (node (ref "U800") (pin "K1") (pinfunction "IO_L38N_M3DQ3_3_K1") (pintype "bidirectional"))
    )
    (net (code "2") (name "/AUD6_TFS") (class "Default")
      (node (ref "U800") (pin "A4") (pinfunction "IO_L5N_0_A4") (pintype "bidirectional"))
    )
    (net (code "3") (name "/AUD6_TXC") (class "Default")
      (node (ref "U800") (pin "B4") (pinfunction "IO_L5P_0_B4") (pintype "bidirectional"))
    )
    (net (code "4") (name "/AUD6_TXD") (class "Default")
      (node (ref "U800") (pin "A6") (pinfunction "IO_L8N_VREF_0_A6") (pintype "bidirectional"))
    )
    (net (code "5") (name "/AUD_MCLK") (class "Default")
      (node (ref "U800") (pin "H6") (pinfunction "IO_L49P_M3A7_3_H6") (pintype "bidirectional"))
    )
    (net (code "6") (name "/BATT_NRST") (class "Default")
      (node (ref "U800") (pin "N1") (pinfunction "IO_L35N_M3DQ11_3_N1") (pintype "bidirectional"))
    )
    (net (code "7") (name "/BATT_REFLASH_ALRT") (class "Default")
      (node (ref "U800") (pin "N2") (pinfunction "IO_L35P_M3DQ10_3_N2") (pintype "bidirectional"))
    )
    (net (code "8") (name "/CLK2_N") (class "Default")
      (node (ref "U800") (pin "H1") (pinfunction "IO_L41N_GCLK26_M3DQ5_3_H1") (pintype "bidirectional"))
    )
    (net (code "9") (name "/CLK2_P") (class "Default")
      (node (ref "U800") (pin "H2") (pinfunction "IO_L41P_GCLK27_M3DQ4_3_H2") (pintype "bidirectional"))
    )
    (net (code "10") (name "/CPU_TAMPER") (class "Default")
      (node (ref "R26F") (pin "2") (pinfunction "2_2") (pintype "passive"))
    )
    (net (code "11") (name "/DDC_SCL") (class "Default")
      (node (ref "JP10F") (pin "B3") (pinfunction "B3_B3") (pintype "passive"))
      (node (ref "U800") (pin "J6") (pinfunction "IO_L47N_M3A1_3_J6") (pintype "bidirectional"))
    )
    (net (code "12") (name "/DDC_SDA") (class "Default")
      (node (ref "JP10F") (pin "A5") (pinfunction "A5_A5") (pintype "passive"))
      (node (ref "U800") (pin "F2") (pinfunction "IO_L48P_M3BA0_3_F2") (pintype "bidirectional"))
    )
    (net (code "13") (name "/ECSPI3_MISO") (class "Default")
      (node (ref "U800") (pin "A3") (pinfunction "IO_L4N_0_A3") (pintype "bidirectional"))
    )
    (net (code "14") (name "/ECSPI3_MOSI") (class "Default")
      (node (ref "U800") (pin "A2") (pinfunction "IO_L2N_0_A2") (pintype "bidirectional"))
      (node (ref "U800") (pin "R13") (pinfunction "IO_L3P_D0_DIN_MISO_MISO1_2_R13") (pintype "bidirectional"))
    )
    (net (code "15") (name "/ECSPI3_RDY") (class "Default")
      (node (ref "U800") (pin "A5") (pinfunction "IO_L6N_0_A5") (pintype "bidirectional"))
    )
    (net (code "16") (name "/ECSPI3_SCLK") (class "Default")
      (node (ref "U800") (pin "D9") (pinfunction "IO_L34P_GCLK19_0_D9") (pintype "bidirectional"))
      (node (ref "U800") (pin "R15") (pinfunction "IO_L1P_CCLK_2_R15") (pintype "bidirectional"))
    )
    (net (code "17") (name "/ECSPI3_SS2") (class "Default")
      (node (ref "U800") (pin "B3") (pinfunction "IO_L4P_0_B3") (pintype "bidirectional"))
    )
    (net (code "18") (name "/EIM_A16") (class "Default")
      (node (ref "U800") (pin "A11") (pinfunction "IO_L39N_0_A11") (pintype "bidirectional"))
    )
    (net (code "19") (name "/EIM_A17") (class "Default")
      (node (ref "U800") (pin "B12") (pinfunction "IO_L41P_0_B12") (pintype "bidirectional"))
    )
    (net (code "20") (name "/EIM_A18") (class "Default")
      (node (ref "U800") (pin "D14") (pinfunction "IO_L65P_SCP3_0_D14") (pintype "bidirectional"))
    )
    (net (code "21") (name "/EIM_BCLK") (class "Default")
      (node (ref "U800") (pin "C9") (pinfunction "IO_L34N_GCLK18_0_C9") (pintype "bidirectional"))
    )
    (net (code "22") (name "/EIM_CS0") (class "Default")
      (node (ref "U800") (pin "B11") (pinfunction "IO_L39P_0_B11") (pintype "bidirectional"))
    )
    (net (code "23") (name "/EIM_CS1") (class "Default")
      (node (ref "U800") (pin "A15") (pinfunction "IO_L64N_SCP4_0_A15") (pintype "bidirectional"))
    )
    (net (code "24") (name "/EIM_DA0") (class "Default")
      (node (ref "U800") (pin "G9") (pinfunction "IO_L38P_0_G9") (pintype "bidirectional"))
    )
    (net (code "25") (name "/EIM_DA1") (class "Default")
      (node (ref "U800") (pin "A10") (pinfunction "IO_L37N_GCLK12_0_A10") (pintype "bidirectional"))
    )
    (net (code "26") (name "/EIM_DA2") (class "Default")
      (node (ref "U800") (pin "F9") (pinfunction "IO_L38N_VREF_0_F9") (pintype "bidirectional"))
    )
    (net (code "27") (name "/EIM_DA3") (class "Default")
      (node (ref "U800") (pin "B9") (pinfunction "IO_L35P_GCLK17_0_B9") (pintype "bidirectional"))
    )
    (net (code "28") (name "/EIM_DA4") (class "Default")
      (node (ref "U800") (pin "E13") (pinfunction "IO_L63N_SCP6_0_E13") (pintype "bidirectional"))
    )
    (net (code "29") (name "/EIM_DA5") (class "Default")
      (node (ref "U800") (pin "F13") (pinfunction "IO_L63P_SCP7_0_F13") (pintype "bidirectional"))
    )
    (net (code "30") (name "/EIM_DA6") (class "Default")
      (node (ref "U800") (pin "A9") (pinfunction "IO_L35N_GCLK16_0_A9") (pintype "bidirectional"))
    )
    (net (code "31") (name "/EIM_DA7") (class "Default")
      (node (ref "U800") (pin "A8") (pinfunction "IO_L33N_0_A8") (pintype "bidirectional"))
    )
    (net (code "32") (name "/EIM_DA8") (class "Default")
      (node (ref "U800") (pin "B8") (pinfunction "IO_L33P_0_B8") (pintype "bidirectional"))
    )
    (net (code "33") (name "/EIM_DA9") (class "Default")
      (node (ref "U800") (pin "D8") (pinfunction "IO_L11P_0_D8") (pintype "bidirectional"))
    )
    (net (code "34") (name "/EIM_DA10") (class "Default")
      (node (ref "U800") (pin "D11") (pinfunction "IO_L36P_GCLK15_0_D11") (pintype "bidirectional"))
    )
    (net (code "35") (name "/EIM_DA11") (class "Default")
      (node (ref "U800") (pin "C8") (pinfunction "IO_L11N_0_C8") (pintype "bidirectional"))
    )
    (net (code "36") (name "/EIM_DA12") (class "Default")
      (node (ref "U800") (pin "C7") (pinfunction "IO_L10P_0_C7") (pintype "bidirectional"))
    )
    (net (code "37") (name "/EIM_DA13") (class "Default")
      (node (ref "U800") (pin "C11") (pinfunction "IO_L36N_GCLK14_0_C11") (pintype "bidirectional"))
    )
    (net (code "38") (name "/EIM_DA14") (class "Default")
      (node (ref "U800") (pin "C4") (pinfunction "IO_L1N_VREF_0_C4") (pintype "bidirectional"))
    )
    (net (code "39") (name "/EIM_DA15") (class "Default")
      (node (ref "U800") (pin "B6") (pinfunction "IO_L8P_0_B6") (pintype "bidirectional"))
    )
    (net (code "40") (name "/EIM_LBA") (class "Default")
      (node (ref "U800") (pin "B14") (pinfunction "IO_L62P_0_B14") (pintype "bidirectional"))
    )
    (net (code "41") (name "/EIM_OE") (class "Default")
      (node (ref "U800") (pin "C10") (pinfunction "IO_L37P_GCLK13_0_C10") (pintype "bidirectional"))
    )
    (net (code "42") (name "/EIM_RW") (class "Default")
      (node (ref "U800") (pin "C14") (pinfunction "IO_L65N_SCP2_0_C14") (pintype "bidirectional"))
    )
    (net (code "43") (name "/EIM_WAIT") (class "Default")
      (node (ref "U800") (pin "A7") (pinfunction "IO_L10N_0_A7") (pintype "bidirectional"))
    )
    (net (code "44") (name "/FDDR3_VREF") (class "Default")
      (node (ref "C67F") (pin "1") (pinfunction "1_1") (pintype "passive"))
      (node (ref "C68F") (pin "1") (pinfunction "1_1") (pintype "passive"))
      (node (ref "C69F") (pin "1") (pinfunction "1_1") (pintype "passive"))
      (node (ref "C92F") (pin "1") (pinfunction "1_1") (pintype "passive"))
      (node (ref "C93F") (pin "1") (pinfunction "1_1") (pintype "passive"))
      (node (ref "C94F") (pin "2") (pinfunction "2_2") (pintype "passive"))
      (node (ref "R10F") (pin "2") (pinfunction "2_2") (pintype "passive"))
      (node (ref "R11F") (pin "2") (pinfunction "2_2") (pintype "passive"))
      (node (ref "R29F") (pin "1") (pinfunction "1_1") (pintype "passive"))
      (node (ref "U12F") (pin "H1") (pinfunction "VREFDQ_H1") (pintype "input"))
      (node (ref "U12F") (pin "M8") (pinfunction "VREFCA_M8") (pintype "input"))
      (node (ref "U800") (pin "F16") (pinfunction "IO_L1N_A24_VREF_1_F16") (pintype "bidirectional"))
      (node (ref "U800") (pin "N14") (pinfunction "IO_L53N_VREF_1_N14") (pintype "bidirectional"))
    )
    (net (code "45") (name "/FPGA_DONE") (class "Default")
      (node (ref "R22F") (pin "1") (pinfunction "1_1") (pintype "passive"))
      (node (ref "U800") (pin "V17") (pinfunction "DONE_2_V17") (pintype "bidirectional"))
    )
    (net (code "46") (name "/FPGA_EXP_ON") (class "Default")
      (node (ref "Q12F") (pin "1") (pinfunction "G_1") (pintype "passive"))
      (node (ref "R36F") (pin "2") (pinfunction "2_2") (pintype "passive"))
    )
    (net (code "47") (name "/FPGA_HSWAPEN") (class "Default")
      (node (ref "R12F") (pin "2") (pinfunction "2_2") (pintype "passive"))
      (node (ref "R13F") (pin "1") (pinfunction "1_1") (pintype "passive"))
      (node (ref "U800") (pin "D4") (pinfunction "IO_L1P_HSWAPEN_0_D4") (pintype "bidirectional"))
    )
    (net (code "48") (name "/FPGA_INIT_N") (class "Default")
      (node (ref "R21F") (pin "2") (pinfunction "2_2") (pintype "passive"))
      (node (ref "U800") (pin "U3") (pinfunction "IO_L65P_INIT_B_2_U3") (pintype "bidirectional"))
    )
    (net (code "49") (name "/FPGA_LED2") (class "Default")
      (node (ref "D12F") (pin "1") (pinfunction "A_1") (pintype "passive"))
      (node (ref "U800") (pin "A16") (pinfunction "IO_L66N_SCP0_0_A16") (pintype "bidirectional"))
    )
    (net (code "50") (name "/FPGA_LSPI_CLK") (class "Default")
      (node (ref "U800") (pin "D3") (pinfunction "IO_L54N_M3A11_3_D3") (pintype "bidirectional"))
    )
    (net (code "51") (name "/FPGA_LSPI_CS") (class "Default")
      (node (ref "U800") (pin "D1") (pinfunction "IO_L52N_M3A9_3_D1") (pintype "bidirectional"))
    )
    (net (code "52") (name "/FPGA_LSPI_HOLD") (class "Default")
      (node (ref "U800") (pin "E3") (pinfunction "IO_L50P_M3WE_3_E3") (pintype "bidirectional"))
    )
    (net (code "53") (name "/FPGA_LSPI_MISO") (class "Default")
      (node (ref "U800") (pin "D2") (pinfunction "IO_L52P_M3A8_3_D2") (pintype "bidirectional"))
    )
    (net (code "54") (name "/FPGA_LSPI_MOSI") (class "Default")
      (node (ref "U800") (pin "C2") (pinfunction "IO_L83P_3_C2") (pintype "bidirectional"))
    )
    (net (code "55") (name "/FPGA_LSPI_WP") (class "Default")
      (node (ref "U800") (pin "C1") (pinfunction "IO_L83N_VREF_3_C1") (pintype "bidirectional"))
    )
    (net (code "56") (name "/FPGA_M0") (class "Default")
      (node (ref "R14F") (pin "2") (pinfunction "2_2") (pintype "passive"))
      (node (ref "R15F") (pin "2") (pinfunction "2_2") (pintype "passive"))
      (node (ref "U800") (pin "T15") (pinfunction "IO_L1N_M0_CMPMISO_2_T15") (pintype "bidirectional"))
    )
    (net (code "57") (name "/FPGA_M1") (class "Default")
      (node (ref "R16F") (pin "2") (pinfunction "2_2") (pintype "passive"))
      (node (ref "R17F") (pin "2") (pinfunction "2_2") (pintype "passive"))
      (node (ref "U800") (pin "N12") (pinfunction "IO_L13P_M1_2_N12") (pintype "bidirectional"))
    )
    (net (code "58") (name "/FPGA_RESET_N") (class "Default")
      (node (ref "R25F") (pin "1") (pinfunction "1_1") (pintype "passive"))
      (node (ref "U11F") (pin "6") (pinfunction "C_6") (pintype "input"))
      (node (ref "U800") (pin "V2") (pinfunction "PROGRAM_B_2_V2") (pintype "input"))
    )
    (net (code "59") (name "/FPGA_SUSPEND") (class "Default")
      (node (ref "R23F") (pin "2") (pinfunction "2_2") (pintype "passive"))
      (node (ref "U800") (pin "R16") (pinfunction "SUSPEND_R16") (pintype "input"))
    )
    (net (code "60") (name "/FPGA_TCK") (class "Default")
      (node (ref "P10F") (pin "2") (pinfunction "2_2") (pintype "passive"))
      (node (ref "U800") (pin "A17") (pinfunction "TCK_A17") (pintype "input"))
    )
    (net (code "61") (name "/FPGA_TDI") (class "Default")
      (node (ref "P10F") (pin "3") (pinfunction "3_3") (pintype "passive"))
      (node (ref "U800") (pin "D15") (pinfunction "TDI_D15") (pintype "input"))
    )
    (net (code "62") (name "/FPGA_TDO") (class "Default")
      (node (ref "P10F") (pin "4") (pinfunction "4_4") (pintype "passive"))
      (node (ref "U800") (pin "D16") (pinfunction "TDO_D16") (pintype "output"))
    )
    (net (code "63") (name "/FPGA_TMS") (class "Default")
      (node (ref "P10F") (pin "5") (pinfunction "5_5") (pintype "passive"))
      (node (ref "U800") (pin "B18") (pinfunction "TMS_B18") (pintype "input"))
    )
    (net (code "64") (name "/F_BA0") (class "Default")
      (node (ref "U12F") (pin "M2") (pinfunction "BA0_M2") (pintype "input"))
      (node (ref "U800") (pin "H13") (pinfunction "IO_L36P_A9_M1BA0_1_H13") (pintype "bidirectional"))
    )
    (net (code "65") (name "/F_BA1") (class "Default")
      (node (ref "U12F") (pin "N8") (pinfunction "BA1_N8") (pintype "input"))
      (node (ref "U800") (pin "H14") (pinfunction "IO_L36N_A8_M1BA1_1_H14") (pintype "bidirectional"))
    )
    (net (code "66") (name "/F_BA2") (class "Default")
      (node (ref "U12F") (pin "M3") (pinfunction "BA2_M3") (pintype "input"))
      (node (ref "U800") (pin "K13") (pinfunction "IO_L34N_A12_M1BA2_1_K13") (pintype "bidirectional"))
    )
    (net (code "67") (name "/F_CAS_N") (class "Default")
      (node (ref "U12F") (pin "K3") (pinfunction "CAS#_K3") (pintype "input"))
      (node (ref "U800") (pin "K16") (pinfunction "IO_L41N_GCLK8_M1CASN_1_K16") (pintype "bidirectional"))
    )
    (net (code "68") (name "/F_DDR3_A0") (class "Default")
      (node (ref "U12F") (pin "N3") (pinfunction "A0_N3") (pintype "input"))
      (node (ref "U800") (pin "H15") (pinfunction "IO_L37P_A7_M1A0_1_H15") (pintype "bidirectional"))
    )
    (net (code "69") (name "/F_DDR3_A1") (class "Default")
      (node (ref "U12F") (pin "P7") (pinfunction "A1_P7") (pintype "input"))
      (node (ref "U800") (pin "H16") (pinfunction "IO_L37N_A6_M1A1_1_H16") (pintype "bidirectional"))
    )
    (net (code "70") (name "/F_DDR3_A2") (class "Default")
      (node (ref "U12F") (pin "P3") (pinfunction "A2_P3") (pintype "input"))
      (node (ref "U800") (pin "F18") (pinfunction "IO_L35N_A10_M1A2_1_F18") (pintype "bidirectional"))
    )
    (net (code "71") (name "/F_DDR3_A3") (class "Default")
      (node (ref "U12F") (pin "N2") (pinfunction "A3_N2") (pintype "input"))
      (node (ref "U800") (pin "J13") (pinfunction "IO_L39P_M1A3_1_J13") (pintype "bidirectional"))
    )
    (net (code "72") (name "/F_DDR3_A4") (class "Default")
      (node (ref "U12F") (pin "P8") (pinfunction "A4_P8") (pintype "input"))
      (node (ref "U800") (pin "E18") (pinfunction "IO_L33N_A14_M1A4_1_E18") (pintype "bidirectional"))
    )
    (net (code "73") (name "/F_DDR3_A5") (class "Default")
      (node (ref "U12F") (pin "P2") (pinfunction "A5_P2") (pintype "input"))
      (node (ref "U800") (pin "L12") (pinfunction "IO_L40P_GCLK11_M1A5_1_L12") (pintype "bidirectional"))
    )
    (net (code "74") (name "/F_DDR3_A6") (class "Default")
      (node (ref "U12F") (pin "R8") (pinfunction "A6_R8") (pintype "input"))
      (node (ref "U800") (pin "L13") (pinfunction "IO_L40N_GCLK10_M1A6_1_L13") (pintype "bidirectional"))
    )
    (net (code "75") (name "/F_DDR3_A7") (class "Default")
      (node (ref "U12F") (pin "R2") (pinfunction "A7_R2") (pintype "input"))
      (node (ref "U800") (pin "F17") (pinfunction "IO_L35P_A11_M1A7_1_F17") (pintype "bidirectional"))
    )
    (net (code "76") (name "/F_DDR3_A8") (class "Default")
      (node (ref "U12F") (pin "T8") (pinfunction "A8_T8") (pintype "input"))
      (node (ref "U800") (pin "H12") (pinfunction "IO_L32P_A17_M1A8_1_H12") (pintype "bidirectional"))
    )
    (net (code "77") (name "/F_DDR3_A9") (class "Default")
      (node (ref "U12F") (pin "R3") (pinfunction "A9_R3") (pintype "input"))
      (node (ref "U800") (pin "G13") (pinfunction "IO_L32N_A16_M1A9_1_G13") (pintype "bidirectional"))
    )
    (net (code "78") (name "/F_DDR3_A10") (class "Default")
      (node (ref "U12F") (pin "L7") (pinfunction "A10/AP_L7") (pintype "input"))
      (node (ref "U800") (pin "E16") (pinfunction "IO_L33P_A15_M1A10_1_E16") (pintype "bidirectional"))
    )
    (net (code "79") (name "/F_DDR3_A11") (class "Default")
      (node (ref "U12F") (pin "R7") (pinfunction "A11_R7") (pintype "input"))
      (node (ref "U800") (pin "G14") (pinfunction "IO_L30N_A20_M1A11_1_G14") (pintype "bidirectional"))
    )
    (net (code "80") (name "/F_DDR3_A12") (class "Default")
      (node (ref "U12F") (pin "N7") (pinfunction "A12/BC#_N7") (pintype "input"))
      (node (ref "U800") (pin "D18") (pinfunction "IO_L31N_A18_M1A12_1_D18") (pintype "bidirectional"))
    )
    (net (code "81") (name "/F_DDR3_A13") (class "Default")
      (node (ref "U12F") (pin "T3") (pinfunction "A13_T3") (pintype "input"))
      (node (ref "U800") (pin "C17") (pinfunction "IO_L29P_A23_M1A13_1_C17") (pintype "bidirectional"))
    )
    (net (code "82") (name "/F_DDR3_CKE") (class "Default")
      (node (ref "R32F") (pin "2") (pinfunction "2_2") (pintype "passive"))
      (node (ref "U12F") (pin "K9") (pinfunction "CKE_K9") (pintype "input"))
      (node (ref "U800") (pin "D17") (pinfunction "IO_L31P_A19_M1CKE_1_D17") (pintype "bidirectional"))
    )
    (net (code "83") (name "/F_DDR3_CK_N") (class "Default")
      (node (ref "R31F") (pin "1") (pinfunction "1_1") (pintype "passive"))
      (node (ref "U12F") (pin "K7") (pinfunction "CK#_K7") (pintype "input"))
      (node (ref "U800") (pin "G18") (pinfunction "IO_L38N_A4_M1CLKN_1_G18") (pintype "bidirectional"))
    )
    (net (code "84") (name "/F_DDR3_CK_P") (class "Default")
      (node (ref "R31F") (pin "2") (pinfunction "2_2") (pintype "passive"))
      (node (ref "U12F") (pin "J7") (pinfunction "CK_J7") (pintype "input"))
      (node (ref "U800") (pin "G16") (pinfunction "IO_L38P_A5_M1CLK_1_G16") (pintype "bidirectional"))
    )
    (net (code "85") (name "/F_DDR3_D0") (class "Default")
      (node (ref "U12F") (pin "E3") (pinfunction "DQ0_E3") (pintype "bidirectional"))
      (node (ref "U800") (pin "M16") (pinfunction "IO_L47P_FWE_B_M1DQ0_1_M16") (pintype "bidirectional"))
    )
    (net (code "86") (name "/F_DDR3_D1") (class "Default")
      (node (ref "U12F") (pin "F7") (pinfunction "DQ1_F7") (pintype "bidirectional"))
      (node (ref "U800") (pin "M18") (pinfunction "IO_L47N_LDC_M1DQ1_1_M18") (pintype "bidirectional"))
    )
    (net (code "87") (name "/F_DDR3_D2") (class "Default")
      (node (ref "U12F") (pin "F2") (pinfunction "DQ2_F2") (pintype "bidirectional"))
      (node (ref "U800") (pin "L17") (pinfunction "IO_L46P_FCS_B_M1DQ2_1_L17") (pintype "bidirectional"))
    )
    (net (code "88") (name "/F_DDR3_D3") (class "Default")
      (node (ref "U12F") (pin "F8") (pinfunction "DQ3_F8") (pintype "bidirectional"))
      (node (ref "U800") (pin "L18") (pinfunction "IO_L46N_FOE_B_M1DQ3_1_L18") (pintype "bidirectional"))
    )
    (net (code "89") (name "/F_DDR3_D4") (class "Default")
      (node (ref "U12F") (pin "H3") (pinfunction "DQ4_H3") (pintype "bidirectional"))
      (node (ref "U800") (pin "H17") (pinfunction "IO_L43P_GCLK5_M1DQ4_1_H17") (pintype "bidirectional"))
    )
    (net (code "90") (name "/F_DDR3_D5") (class "Default")
      (node (ref "U12F") (pin "H8") (pinfunction "DQ5_H8") (pintype "bidirectional"))
      (node (ref "U800") (pin "H18") (pinfunction "IO_L43N_GCLK4_M1DQ5_1_H18") (pintype "bidirectional"))
    )
    (net (code "91") (name "/F_DDR3_D6") (class "Default")
      (node (ref "U12F") (pin "G2") (pinfunction "DQ6_G2") (pintype "bidirectional"))
      (node (ref "U800") (pin "J16") (pinfunction "IO_L44P_A3_M1DQ6_1_J16") (pintype "bidirectional"))
    )
    (net (code "92") (name "/F_DDR3_D7") (class "Default")
      (node (ref "U12F") (pin "H7") (pinfunction "DQ7_H7") (pintype "bidirectional"))
      (node (ref "U800") (pin "J18") (pinfunction "IO_L44N_A2_M1DQ7_1_J18") (pintype "bidirectional"))
    )
    (net (code "93") (name "/F_DDR3_D8") (class "Default")
      (node (ref "U12F") (pin "D7") (pinfunction "DQ8_D7") (pintype "bidirectional"))
      (node (ref "U800") (pin "N17") (pinfunction "IO_L48P_HDC_M1DQ8_1_N17") (pintype "bidirectional"))
    )
    (net (code "94") (name "/F_DDR3_D9") (class "Default")
      (node (ref "U12F") (pin "C3") (pinfunction "DQ9_C3") (pintype "bidirectional"))
      (node (ref "U800") (pin "N18") (pinfunction "IO_L48N_M1DQ9_1_N18") (pintype "bidirectional"))
    )
    (net (code "95") (name "/F_DDR3_D10") (class "Default")
      (node (ref "U12F") (pin "C8") (pinfunction "DQ10_C8") (pintype "bidirectional"))
      (node (ref "U800") (pin "P17") (pinfunction "IO_L49P_M1DQ10_1_P17") (pintype "bidirectional"))
    )
    (net (code "96") (name "/F_DDR3_D11") (class "Default")
      (node (ref "U12F") (pin "C2") (pinfunction "DQ11_C2") (pintype "bidirectional"))
      (node (ref "U800") (pin "P18") (pinfunction "IO_L49N_M1DQ11_1_P18") (pintype "bidirectional"))
    )
    (net (code "97") (name "/F_DDR3_D12") (class "Default")
      (node (ref "U12F") (pin "A7") (pinfunction "DQ12_A7") (pintype "bidirectional"))
      (node (ref "U800") (pin "T17") (pinfunction "IO_L51P_M1DQ12_1_T17") (pintype "bidirectional"))
    )
    (net (code "98") (name "/F_DDR3_D13") (class "Default")
      (node (ref "U12F") (pin "A2") (pinfunction "DQ13_A2") (pintype "bidirectional"))
      (node (ref "U800") (pin "T18") (pinfunction "IO_L51N_M1DQ13_1_T18") (pintype "bidirectional"))
    )
    (net (code "99") (name "/F_DDR3_D14") (class "Default")
      (node (ref "U12F") (pin "B8") (pinfunction "DQ14_B8") (pintype "bidirectional"))
      (node (ref "U800") (pin "U17") (pinfunction "IO_L52P_M1DQ14_1_U17") (pintype "bidirectional"))
    )
    (net (code "100") (name "/F_DDR3_D15") (class "Default")
      (node (ref "U12F") (pin "A3") (pinfunction "DQ15_A3") (pintype "bidirectional"))
      (node (ref "U800") (pin "U18") (pinfunction "IO_L52N_M1DQ15_1_U18") (pintype "bidirectional"))
    )
    (net (code "101") (name "/F_DDR3_ODT") (class "Default")
      (node (ref "U12F") (pin "K1") (pinfunction "ODT_K1") (pintype "input"))
      (node (ref "U800") (pin "K14") (pinfunction "IO_L39N_M1ODT_1_K14") (pintype "bidirectional"))
    )
    (net (code "102") (name "/F_DDR3_RST_N") (class "Default")
      (node (ref "R33F") (pin "2") (pinfunction "2_2") (pintype "passive"))
      (node (ref "U12F") (pin "T2") (pinfunction "RESET#_T2") (pintype "input"))
      (node (ref "U800") (pin "F14") (pinfunction "IO_L30P_A21_M1RESET_1_F14") (pintype "bidirectional"))
    )
    (net (code "103") (name "/F_DDR3_RZQ") (class "Default")
      (node (ref "R28F") (pin "2") (pinfunction "2_2") (pintype "passive"))
      (node (ref "U800") (pin "F15") (pinfunction "IO_L1P_A25_1_F15") (pintype "bidirectional"))
    )
    (net (code "104") (name "/F_DDR3_ZIO") (class "Default")
      (node (ref "U800") (pin "M14") (pinfunction "IO_L53P_1_M14") (pintype "bidirectional+no_connect"))
    )
    (net (code "105") (name "/F_DDR3_ZQ") (class "Default")
      (node (ref "R34F") (pin "2") (pinfunction "2_2") (pintype "passive"))
      (node (ref "U12F") (pin "L8") (pinfunction "ZQ_L8") (pintype "input"))
    )
    (net (code "106") (name "/F_DX0") (class "Default")
      (node (ref "JP10F") (pin "A1") (pinfunction "A1_A1") (pintype "passive"))
      (node (ref "U800") (pin "K6") (pinfunction "IO_L45N_M3ODT_3_K6") (pintype "bidirectional"))
    )
    (net (code "107") (name "/F_DX1") (class "Default")
      (node (ref "JP10F") (pin "A8") (pinfunction "A8_A8") (pintype "passive"))
      (node (ref "U800") (pin "L7") (pinfunction "IO_L45P_M3A3_3_L7") (pintype "bidirectional"))
    )
    (net (code "108") (name "/F_DX2") (class "Default")
      (node (ref "JP10F") (pin "A3") (pinfunction "A3_A3") (pintype "passive"))
      (node (ref "U800") (pin "H3") (pinfunction "IO_L44N_GCLK20_M3A6_3_H3") (pintype "bidirectional"))
    )
    (net (code "109") (name "/F_DX3") (class "Default")
      (node (ref "JP10F") (pin "A2") (pinfunction "A2_A2") (pintype "passive"))
      (node (ref "U800") (pin "H4") (pinfunction "IO_L44P_GCLK21_M3A5_3_H4") (pintype "bidirectional"))
    )
    (net (code "110") (name "/F_DX4") (class "Default")
      (node (ref "JP10F") (pin "B2") (pinfunction "B2_B2") (pintype "passive"))
      (node (ref "U800") (pin "J1") (pinfunction "IO_L40N_M3DQ7_3_J1") (pintype "bidirectional"))
    )
    (net (code "111") (name "/F_DX5") (class "Default")
      (node (ref "JP10F") (pin "B1") (pinfunction "B1_B1") (pintype "passive"))
      (node (ref "U800") (pin "J3") (pinfunction "IO_L40P_M3DQ6_3_J3") (pintype "bidirectional"))
    )
    (net (code "112") (name "/F_DX6") (class "Default")
      (node (ref "JP10F") (pin "B39") (pinfunction "B39_B39") (pintype "passive"))
      (node (ref "U800") (pin "L3") (pinfunction "IO_L39N_M3LDQSN_3_L3") (pintype "bidirectional"))
    )
    (net (code "113") (name "/F_DX7") (class "Default")
      (node (ref "JP10F") (pin "B37") (pinfunction "B37_B37") (pintype "passive"))
      (node (ref "U800") (pin "L4") (pinfunction "IO_L39P_M3LDQS_3_L4") (pintype "bidirectional"))
    )
    (net (code "114") (name "/F_DX8") (class "Default")
      (node (ref "JP10F") (pin "B6") (pinfunction "B6_B6") (pintype "passive"))
      (node (ref "U800") (pin "K2") (pinfunction "IO_L38P_M3DQ2_3_K2") (pintype "bidirectional"))
    )
    (net (code "115") (name "/F_DX11") (class "Default")
      (node (ref "JP10F") (pin "A4") (pinfunction "A4_A4") (pintype "passive"))
      (node (ref "U800") (pin "M1") (pinfunction "IO_L36N_M3DQ9_3_M1") (pintype "bidirectional"))
    )
    (net (code "116") (name "/F_DX12") (class "Default")
      (node (ref "JP10F") (pin "B38") (pinfunction "B38_B38") (pintype "passive"))
      (node (ref "U800") (pin "M3") (pinfunction "IO_L36P_M3DQ8_3_M3") (pintype "bidirectional"))
    )
    (net (code "117") (name "/F_DX13") (class "Default")
      (node (ref "JP10F") (pin "B40") (pinfunction "B40_B40") (pintype "passive"))
      (node (ref "U800") (pin "P2") (pinfunction "IO_L34P_M3UDQS_3_P2") (pintype "bidirectional"))
    )
    (net (code "118") (name "/F_DX14") (class "Default")
      (node (ref "JP10F") (pin "A25") (pinfunction "A25_A25") (pintype "passive"))
      (node (ref "U800") (pin "T2") (pinfunction "IO_L33P_M3DQ12_3_T2") (pintype "bidirectional"))
    )
    (net (code "119") (name "/F_DX15") (class "Default")
      (node (ref "JP10F") (pin "B36") (pinfunction "B36_B36") (pintype "passive"))
      (node (ref "U800") (pin "M5") (pinfunction "IO_L31N_VREF_3_M5") (pintype "bidirectional"))
    )
    (net (code "120") (name "/F_DX16") (class "Default")
      (node (ref "JP10F") (pin "B10") (pinfunction "B10_B10") (pintype "passive"))
      (node (ref "U800") (pin "L6") (pinfunction "IO_L31P_3_L6") (pintype "bidirectional"))
    )
    (net (code "121") (name "/F_DX17") (class "Default")
      (node (ref "JP10F") (pin "A12") (pinfunction "A12_A12") (pintype "passive"))
      (node (ref "U800") (pin "G1") (pinfunction "IO_L46N_M3CLKN_3_G1") (pintype "bidirectional"))
    )
    (net (code "122") (name "/F_DX18") (class "Default")
      (node (ref "JP10F") (pin "B16") (pinfunction "B16_B16") (pintype "passive"))
      (node (ref "U800") (pin "H7") (pinfunction "IO_L53P_M3CKE_3_H7") (pintype "bidirectional"))
    )
    (net (code "123") (name "/F_LDM") (class "Default")
      (node (ref "U12F") (pin "E7") (pinfunction "LDM_E7") (pintype "input"))
      (node (ref "U800") (pin "L16") (pinfunction "IO_L42N_GCLK6_TRDY1_M1LDM_1_L16") (pintype "bidirectional"))
    )
    (net (code "124") (name "/F_LDQS_N") (class "Default")
      (node (ref "U12F") (pin "G3") (pinfunction "LDQS#_G3") (pintype "bidirectional"))
      (node (ref "U800") (pin "K18") (pinfunction "IO_L45N_A0_M1LDQSN_1_K18") (pintype "bidirectional"))
    )
    (net (code "125") (name "/F_LDQS_P") (class "Default")
      (node (ref "U12F") (pin "F3") (pinfunction "LDQS_F3") (pintype "bidirectional"))
      (node (ref "U800") (pin "K17") (pinfunction "IO_L45P_A1_M1LDQS_1_K17") (pintype "bidirectional"))
    )
    (net (code "126") (name "/F_LVDS0_N") (class "Default")
      (node (ref "JP10F") (pin "A20") (pinfunction "A20_A20") (pintype "passive"))
      (node (ref "U800") (pin "P6") (pinfunction "IO_L64N_D9_2_P6") (pintype "bidirectional"))
    )
    (net (code "127") (name "/F_LVDS0_P") (class "Default")
      (node (ref "JP10F") (pin "A19") (pinfunction "A19_A19") (pintype "passive"))
      (node (ref "U800") (pin "N5") (pinfunction "IO_L64P_D8_2_N5") (pintype "bidirectional"))
    )
    (net (code "128") (name "/F_LVDS1_N") (class "Default")
      (node (ref "JP10F") (pin "A30") (pinfunction "A30_A30") (pintype "passive"))
      (node (ref "U800") (pin "V4") (pinfunction "IO_L63N_2_V4") (pintype "bidirectional"))
    )
    (net (code "129") (name "/F_LVDS1_P") (class "Default")
      (node (ref "JP10F") (pin "A29") (pinfunction "A29_A29") (pintype "passive"))
      (node (ref "U800") (pin "T4") (pinfunction "IO_L63P_2_T4") (pintype "bidirectional"))
    )
    (net (code "130") (name "/F_LVDS2_N") (class "Default")
      (node (ref "JP10F") (pin "A32") (pinfunction "A32_A32") (pintype "passive"))
      (node (ref "U800") (pin "T3") (pinfunction "IO_L62N_D6_2_T3") (pintype "bidirectional"))
    )
    (net (code "131") (name "/F_LVDS2_P") (class "Default")
      (node (ref "JP10F") (pin "A33") (pinfunction "A33_A33") (pintype "passive"))
      (node (ref "U800") (pin "R3") (pinfunction "IO_L62P_D5_2_R3") (pintype "bidirectional"))
    )
    (net (code "132") (name "/F_LVDS3_N") (class "Default")
      (node (ref "JP10F") (pin "B31") (pinfunction "B31_B31") (pintype "passive"))
      (node (ref "U800") (pin "V5") (pinfunction "IO_L49N_D4_2_V5") (pintype "bidirectional"))
    )
    (net (code "133") (name "/F_LVDS3_P") (class "Default")
      (node (ref "JP10F") (pin "B32") (pinfunction "B32_B32") (pintype "passive"))
      (node (ref "U800") (pin "U5") (pinfunction "IO_L49P_D3_2_U5") (pintype "bidirectional"))
    )
    (net (code "134") (name "/F_LVDS4_N") (class "Default")
      (node (ref "JP10F") (pin "A27") (pinfunction "A27_A27") (pintype "passive"))
      (node (ref "U800") (pin "T5") (pinfunction "IO_L48N_RDWR_B_VREF_2_T5") (pintype "bidirectional"))
    )
    (net (code "135") (name "/F_LVDS4_P") (class "Default")
      (node (ref "JP10F") (pin "A26") (pinfunction "A26_A26") (pintype "passive"))
      (node (ref "U800") (pin "R5") (pinfunction "IO_L48P_D7_2_R5") (pintype "bidirectional"))
    )
    (net (code "136") (name "/F_LVDS5_N") (class "Default")
      (node (ref "JP10F") (pin "B27") (pinfunction "B27_B27") (pintype "passive"))
      (node (ref "U800") (pin "T7") (pinfunction "IO_L46N_2_T7") (pintype "bidirectional"))
    )
    (net (code "137") (name "/F_LVDS5_P") (class "Default")
      (node (ref "JP10F") (pin "B26") (pinfunction "B26_B26") (pintype "passive"))
      (node (ref "U800") (pin "R7") (pinfunction "IO_L46P_2_R7") (pintype "bidirectional"))
    )
    (net (code "138") (name "/F_LVDS6_N") (class "Default")
      (node (ref "JP10F") (pin "B28") (pinfunction "B28_B28") (pintype "passive"))
      (node (ref "U800") (pin "V6") (pinfunction "IO_L45N_2_V6") (pintype "bidirectional"))
    )
    (net (code "139") (name "/F_LVDS6_P") (class "Default")
      (node (ref "JP10F") (pin "B29") (pinfunction "B29_B29") (pintype "passive"))
      (node (ref "U800") (pin "T6") (pinfunction "IO_L45P_2_T6") (pintype "bidirectional"))
    )
    (net (code "140") (name "/F_LVDS7_N") (class "Default")
      (node (ref "JP10F") (pin "B35") (pinfunction "B35_B35") (pintype "passive"))
      (node (ref "U800") (pin "V7") (pinfunction "IO_L43N_2_V7") (pintype "bidirectional"))
    )
    (net (code "141") (name "/F_LVDS7_P") (class "Default")
      (node (ref "JP10F") (pin "B34") (pinfunction "B34_B34") (pintype "passive"))
      (node (ref "U800") (pin "U7") (pinfunction "IO_L43P_2_U7") (pintype "bidirectional"))
    )
    (net (code "142") (name "/F_LVDS8_N") (class "Default")
      (node (ref "JP10F") (pin "B25") (pinfunction "B25_B25") (pintype "passive"))
      (node (ref "U800") (pin "V8") (pinfunction "IO_L41N_VREF_2_V8") (pintype "bidirectional"))
    )
    (net (code "143") (name "/F_LVDS8_P") (class "Default")
      (node (ref "JP10F") (pin "B24") (pinfunction "B24_B24") (pintype "passive"))
      (node (ref "U800") (pin "U8") (pinfunction "IO_L41P_2_U8") (pintype "bidirectional"))
    )
    (net (code "144") (name "/F_LVDS9_N") (class "Default")
      (node (ref "JP10F") (pin "B22") (pinfunction "B22_B22") (pintype "passive"))
      (node (ref "U800") (pin "V9") (pinfunction "IO_L32N_GCLK28_2_V9") (pintype "bidirectional"))
    )
    (net (code "145") (name "/F_LVDS9_P") (class "Default")
      (node (ref "JP10F") (pin "B21") (pinfunction "B21_B21") (pintype "passive"))
      (node (ref "U800") (pin "T9") (pinfunction "IO_L32P_GCLK29_2_T9") (pintype "bidirectional"))
    )
    (net (code "146") (name "/F_LVDS10_N") (class "Default")
      (node (ref "JP10F") (pin "B15") (pinfunction "B15_B15") (pintype "passive"))
      (node (ref "U800") (pin "V11") (pinfunction "IO_L23N_2_V11") (pintype "bidirectional"))
    )
    (net (code "147") (name "/F_LVDS10_P") (class "Default")
      (node (ref "JP10F") (pin "B14") (pinfunction "B14_B14") (pintype "passive"))
      (node (ref "U800") (pin "U11") (pinfunction "IO_L23P_2_U11") (pintype "bidirectional"))
    )
    (net (code "148") (name "/F_LVDS11_N") (class "Default")
      (node (ref "JP10F") (pin "A7") (pinfunction "A7_A7") (pintype "passive"))
      (node (ref "U800") (pin "T11") (pinfunction "IO_L16N_VREF_2_T11") (pintype "bidirectional"))
    )
    (net (code "149") (name "/F_LVDS11_P") (class "Default")
      (node (ref "JP10F") (pin "A6") (pinfunction "A6_A6") (pintype "passive"))
      (node (ref "U800") (pin "R11") (pinfunction "IO_L16P_2_R11") (pintype "bidirectional"))
    )
    (net (code "150") (name "/F_LVDS12_N") (class "Default")
      (node (ref "JP10F") (pin "B12") (pinfunction "B12_B12") (pintype "passive"))
      (node (ref "U800") (pin "V13") (pinfunction "IO_L14N_D12_2_V13") (pintype "bidirectional"))
    )
    (net (code "151") (name "/F_LVDS12_P") (class "Default")
      (node (ref "JP10F") (pin "B11") (pinfunction "B11_B11") (pintype "passive"))
      (node (ref "U800") (pin "U13") (pinfunction "IO_L14P_D11_2_U13") (pintype "bidirectional"))
    )
    (net (code "152") (name "/F_LVDS13_N") (class "Default")
      (node (ref "JP10F") (pin "B9") (pinfunction "B9_B9") (pintype "passive"))
      (node (ref "U800") (pin "V14") (pinfunction "IO_L12N_D2_MISO3_2_V14") (pintype "bidirectional"))
    )
    (net (code "153") (name "/F_LVDS13_P") (class "Default")
      (node (ref "JP10F") (pin "B8") (pinfunction "B8_B8") (pintype "passive"))
      (node (ref "U800") (pin "T14") (pinfunction "IO_L12P_D1_MISO2_2_T14") (pintype "bidirectional"))
    )
    (net (code "154") (name "/F_LVDS14_N") (class "Default")
      (node (ref "JP10F") (pin "B5") (pinfunction "B5_B5") (pintype "passive"))
      (node (ref "U800") (pin "V16") (pinfunction "IO_L2N_CMPMOSI_2_V16") (pintype "bidirectional"))
    )
    (net (code "155") (name "/F_LVDS14_P") (class "Default")
      (node (ref "JP10F") (pin "B4") (pinfunction "B4_B4") (pintype "passive"))
      (node (ref "U800") (pin "U16") (pinfunction "IO_L2P_CMPCLK_2_U16") (pintype "bidirectional"))
    )
    (net (code "156") (name "/F_LVDS15_N") (class "Default")
      (node (ref "JP10F") (pin "A17") (pinfunction "A17_A17") (pintype "passive"))
      (node (ref "U800") (pin "V10") (pinfunction "IO_L30N_GCLK0_USERCCLK_2_V10") (pintype "bidirectional"))
    )
    (net (code "157") (name "/F_LVDS15_P") (class "Default")
      (node (ref "JP10F") (pin "A16") (pinfunction "A16_A16") (pintype "passive"))
      (node (ref "U800") (pin "U10") (pinfunction "IO_L30P_GCLK1_D13_2_U10") (pintype "bidirectional"))
    )
    (net (code "158") (name "/F_LVDSA_N") (class "Default")
      (node (ref "JP10F") (pin "A35") (pinfunction "A35_A35") (pintype "passive"))
      (node (ref "U800") (pin "K3") (pinfunction "IO_L42N_GCLK24_M3LDM_3_K3") (pintype "bidirectional"))
    )
    (net (code "159") (name "/F_LVDSA_P") (class "Default")
      (node (ref "JP10F") (pin "A34") (pinfunction "A34_A34") (pintype "passive"))
      (node (ref "U800") (pin "K4") (pinfunction "IO_L42P_GCLK25_TRDY2_M3UDM_3_K4") (pintype "bidirectional"))
    )
    (net (code "160") (name "/F_LVDSB_N") (class "Default")
      (node (ref "JP10F") (pin "A14") (pinfunction "A14_A14") (pintype "passive"))
      (node (ref "U800") (pin "K5") (pinfunction "IO_L43N_GCLK22_IRDY2_M3CASN_3_K5") (pintype "bidirectional"))
    )
    (net (code "161") (name "/F_LVDSB_P") (class "Default")
      (node (ref "JP10F") (pin "A15") (pinfunction "A15_A15") (pintype "passive"))
      (node (ref "U800") (pin "L5") (pinfunction "IO_L43P_GCLK23_M3RASN_3_L5") (pintype "bidirectional"))
    )
    (net (code "162") (name "/F_LVDSC_N") (class "Default")
      (node (ref "JP10F") (pin "A9") (pinfunction "A9_A9") (pintype "passive"))
      (node (ref "U800") (pin "L1") (pinfunction "IO_L37N_M3DQ1_3_L1") (pintype "bidirectional"))
    )
    (net (code "163") (name "/F_LVDSC_P") (class "Default")
      (node (ref "JP10F") (pin "A10") (pinfunction "A10_A10") (pintype "passive"))
      (node (ref "U800") (pin "L2") (pinfunction "IO_L37P_M3DQ0_3_L2") (pintype "bidirectional"))
    )
    (net (code "164") (name "/F_LVDS_CK0_N") (class "Default")
      (node (ref "JP10F") (pin "B19") (pinfunction "B19_B19") (pintype "passive"))
      (node (ref "U800") (pin "T8") (pinfunction "IO_L31N_GCLK30_D15_2_T8") (pintype "bidirectional"))
    )
    (net (code "165") (name "/F_LVDS_CK0_P") (class "Default")
      (node (ref "JP10F") (pin "B18") (pinfunction "B18_B18") (pintype "passive"))
      (node (ref "U800") (pin "R8") (pinfunction "IO_L31P_GCLK31_D14_2_R8") (pintype "bidirectional"))
    )
    (net (code "166") (name "/F_LVDS_CK1_N") (class "Default")
      (node (ref "JP10F") (pin "A23") (pinfunction "A23_A23") (pintype "passive"))
      (node (ref "U800") (pin "T10") (pinfunction "IO_L29N_GCLK2_2_T10") (pintype "bidirectional"))
    )
    (net (code "167") (name "/F_LVDS_CK1_P") (class "Default")
      (node (ref "JP10F") (pin "A22") (pinfunction "A22_A22") (pintype "passive"))
      (node (ref "U800") (pin "R10") (pinfunction "IO_L29P_GCLK3_2_R10") (pintype "bidirectional"))
    )
    (net (code "168") (name "/F_RAS_N") (class "Default")
      (node (ref "U12F") (pin "J3") (pinfunction "RAS#_J3") (pintype "input"))
      (node (ref "U800") (pin "K15") (pinfunction "IO_L41P_GCLK9_IRDY1_M1RASN_1_K15") (pintype "bidirectional"))
    )
    (net (code "169") (name "/F_UDM") (class "Default")
      (node (ref "U12F") (pin "D3") (pinfunction "UDM_D3") (pintype "input"))
      (node (ref "U800") (pin "L15") (pinfunction "IO_L42P_GCLK7_M1UDM_1_L15") (pintype "bidirectional"))
    )
    (net (code "170") (name "/F_UDQS_N") (class "Default")
      (node (ref "U12F") (pin "B7") (pinfunction "UDQS#_B7") (pintype "bidirectional"))
      (node (ref "U800") (pin "N16") (pinfunction "IO_L50N_M1UDQSN_1_N16") (pintype "bidirectional"))
    )
    (net (code "171") (name "/F_UDQS_P") (class "Default")
      (node (ref "U12F") (pin "C7") (pinfunction "UDQS_C7") (pintype "bidirectional"))
      (node (ref "U800") (pin "N15") (pinfunction "IO_L50P_M1UDQS_1_N15") (pintype "bidirectional"))
    )
    (net (code "172") (name "/F_WE_N") (class "Default")
      (node (ref "U12F") (pin "L3") (pinfunction "WE#_L3") (pintype "input"))
      (node (ref "U800") (pin "K12") (pinfunction "IO_L34P_A13_M1WE_1_K12") (pintype "bidirectional"))
    )
    (net (code "173") (name "/I2C3_SCL") (class "Default")
      (node (ref "U800") (pin "P4") (pinfunction "IO_L2P_3_P4") (pintype "bidirectional"))
    )
    (net (code "174") (name "/I2C3_SDA") (class "Default")
      (node (ref "U800") (pin "P3") (pinfunction "IO_L2N_3_P3") (pintype "bidirectional"))
    )
    (net (code "175") (name "/P5.0V_FEXP") (class "Default")
      (node (ref "C82F") (pin "2") (pinfunction "2_2") (pintype "passive"))
      (node (ref "C83F") (pin "1") (pinfunction "1_1") (pintype "passive"))
      (node (ref "JP10F") (pin "A36") (pinfunction "A36_A36") (pintype "passive"))
      (node (ref "JP10F") (pin "A37") (pinfunction "A37_A37") (pintype "passive"))
      (node (ref "JP10F") (pin "A38") (pinfunction "A38_A38") (pintype "passive"))
      (node (ref "JP10F") (pin "A39") (pinfunction "A39_A39") (pintype "passive"))
      (node (ref "JP10F") (pin "A40") (pinfunction "A40_A40") (pintype "passive"))
      (node (ref "Q11F") (pin "5") (pinfunction "D_5") (pintype "passive"))
      (node (ref "Q11F") (pin "6") (pinfunction "D_6") (pintype "passive"))
      (node (ref "Q11F") (pin "7") (pinfunction "D_7") (pintype "passive"))
      (node (ref "Q11F") (pin "8") (pinfunction "D_8") (pintype "passive"))
    )
    (net (code "176") (name "/RESETBMCU") (class "Default")
      (node (ref "Q10F") (pin "3") (pinfunction "D_3") (pintype "passive"))
      (node (ref "U800") (pin "F1") (pinfunction "IO_L48N_M3BA1_3_F1") (pintype "bidirectional"))
    )
    (net (code "177") (name "/SMB_SCL") (class "Default")
      (node (ref "U800") (pin "N3") (pinfunction "IO_L1N_VREF_3_N3") (pintype "bidirectional"))
    )
    (net (code "178") (name "/SMB_SDA") (class "Default")
      (node (ref "U800") (pin "N4") (pinfunction "IO_L1P_3_N4") (pintype "bidirectional"))
    )
    (net (code "179") (name "/UART4_CTS") (class "Default")
      (node (ref "U800") (pin "U1") (pinfunction "IO_L32N_M3DQ15_3_U1") (pintype "bidirectional"))
    )
    (net (code "180") (name "/UART4_RTS") (class "Default")
      (node (ref "U800") (pin "U2") (pinfunction "IO_L32P_M3DQ14_3_U2") (pintype "bidirectional"))
    )
    (net (code "181") (name "/UART4_RXD") (class "Default")
      (node (ref "U800") (pin "T1") (pinfunction "IO_L33N_M3DQ13_3_T1") (pintype "bidirectional"))
    )
    (net (code "182") (name "/UART4_TXD") (class "Default")
      (node (ref "U800") (pin "P1") (pinfunction "IO_L34N_M3UDQSN_3_P1") (pintype "bidirectional"))
    )
    (net (code "183") (name "/UIM_CLK") (class "Default")
      (node (ref "U800") (pin "B16") (pinfunction "IO_L66P_SCP1_0_B16") (pintype "bidirectional"))
    )
    (net (code "184") (name "/UIM_DATA") (class "Default")
      (node (ref "U800") (pin "A12") (pinfunction "IO_L41N_0_A12") (pintype "bidirectional"))
    )
    (net (code "185") (name "/UIM_PWR") (class "Default")
      (node (ref "U800") (pin "C18") (pinfunction "IO_L29N_A22_M1A14_1_C18") (pintype "bidirectional"))
    )
    (net (code "186") (name "/UIM_PWRON") (class "Default")
      (node (ref "U800") (pin "A14") (pinfunction "IO_L62N_VREF_0_A14") (pintype "bidirectional"))
    )
    (net (code "187") (name "/UIM_RESET") (class "Default")
      (node (ref "U800") (pin "C15") (pinfunction "IO_L64P_SCP5_0_C15") (pintype "bidirectional"))
    )
    (net (code "188") (name "/USB_HUB1_RST") (class "Default")
      (node (ref "U800") (pin "C5") (pinfunction "IO_L6P_0_C5") (pintype "bidirectional"))
    )
    (net (code "189") (name "/USB_HUB2_RST") (class "Default")
      (node (ref "U800") (pin "G3") (pinfunction "IO_L46P_M3CLK_3_G3") (pintype "bidirectional"))
    )
    (net (code "190") (name "GND") (class "Default")
      (node (ref "C10F") (pin "2") (pinfunction "2_2") (pintype "passive"))
      (node (ref "C11F") (pin "2") (pinfunction "2_2") (pintype "passive"))
      (node (ref "C12F") (pin "2") (pinfunction "2_2") (pintype "passive"))
      (node (ref "C13F") (pin "2") (pinfunction "2_2") (pintype "passive"))
      (node (ref "C14F") (pin "2") (pinfunction "2_2") (pintype "passive"))
      (node (ref "C15F") (pin "2") (pinfunction "2_2") (pintype "passive"))
      (node (ref "C16F") (pin "2") (pinfunction "2_2") (pintype "passive"))
      (node (ref "C17F") (pin "2") (pinfunction "2_2") (pintype "passive"))
      (node (ref "C18F") (pin "2") (pinfunction "2_2") (pintype "passive"))
      (node (ref "C19F") (pin "2") (pinfunction "2_2") (pintype "passive"))
      (node (ref "C20F") (pin "1") (pinfunction "1_1") (pintype "passive"))
      (node (ref "C21F") (pin "2") (pinfunction "2_2") (pintype "passive"))
      (node (ref "C22F") (pin "2") (pinfunction "2_2") (pintype "passive"))
      (node (ref "C23F") (pin "2") (pinfunction "2_2") (pintype "passive"))
      (node (ref "C24F") (pin "2") (pinfunction "2_2") (pintype "passive"))
      (node (ref "C25F") (pin "2") (pinfunction "2_2") (pintype "passive"))
      (node (ref "C26F") (pin "2") (pinfunction "2_2") (pintype "passive"))
      (node (ref "C27F") (pin "2") (pinfunction "2_2") (pintype "passive"))
      (node (ref "C28F") (pin "2") (pinfunction "2_2") (pintype "passive"))
      (node (ref "C29F") (pin "2") (pinfunction "2_2") (pintype "passive"))
      (node (ref "C30F") (pin "1") (pinfunction "1_1") (pintype "passive"))
      (node (ref "C31F") (pin "2") (pinfunction "2_2") (pintype "passive"))
      (node (ref "C32F") (pin "2") (pinfunction "2_2") (pintype "passive"))
      (node (ref "C33F") (pin "2") (pinfunction "2_2") (pintype "passive"))
      (node (ref "C34F") (pin "2") (pinfunction "2_2") (pintype "passive"))
      (node (ref "C35F") (pin "2") (pinfunction "2_2") (pintype "passive"))
      (node (ref "C36F") (pin "2") (pinfunction "2_2") (pintype "passive"))
      (node (ref "C37F") (pin "2") (pinfunction "2_2") (pintype "passive"))
      (node (ref "C38F") (pin "2") (pinfunction "2_2") (pintype "passive"))
      (node (ref "C39F") (pin "2") (pinfunction "2_2") (pintype "passive"))
      (node (ref "C40F") (pin "1") (pinfunction "1_1") (pintype "passive"))
      (node (ref "C41F") (pin "2") (pinfunction "2_2") (pintype "passive"))
      (node (ref "C42F") (pin "2") (pinfunction "2_2") (pintype "passive"))
      (node (ref "C43F") (pin "2") (pinfunction "2_2") (pintype "passive"))
      (node (ref "C44F") (pin "2") (pinfunction "2_2") (pintype "passive"))
      (node (ref "C45F") (pin "2") (pinfunction "2_2") (pintype "passive"))
      (node (ref "C46F") (pin "2") (pinfunction "2_2") (pintype "passive"))
      (node (ref "C47F") (pin "2") (pinfunction "2_2") (pintype "passive"))
      (node (ref "C48F") (pin "2") (pinfunction "2_2") (pintype "passive"))
      (node (ref "C49F") (pin "1") (pinfunction "1_1") (pintype "passive"))
      (node (ref "C50F") (pin "2") (pinfunction "2_2") (pintype "passive"))
      (node (ref "C51F") (pin "2") (pinfunction "2_2") (pintype "passive"))
      (node (ref "C52F") (pin "2") (pinfunction "2_2") (pintype "passive"))
      (node (ref "C53F") (pin "2") (pinfunction "2_2") (pintype "passive"))
      (node (ref "C54F") (pin "2") (pinfunction "2_2") (pintype "passive"))
      (node (ref "C55F") (pin "2") (pinfunction "2_2") (pintype "passive"))
      (node (ref "C56F") (pin "2") (pinfunction "2_2") (pintype "passive"))
      (node (ref "C57F") (pin "2") (pinfunction "2_2") (pintype "passive"))
      (node (ref "C58F") (pin "2") (pinfunction "2_2") (pintype "passive"))
      (node (ref "C59F") (pin "2") (pinfunction "2_2") (pintype "passive"))
      (node (ref "C60F") (pin "1") (pinfunction "1_1") (pintype "passive"))
      (node (ref "C61F") (pin "2") (pinfunction "2_2") (pintype "passive"))
      (node (ref "C62F") (pin "2") (pinfunction "2_2") (pintype "passive"))
      (node (ref "C63F") (pin "2") (pinfunction "2_2") (pintype "passive"))
      (node (ref "C65F") (pin "1") (pinfunction "1_1") (pintype "passive"))
      (node (ref "C66F") (pin "2") (pinfunction "2_2") (pintype "passive"))
      (node (ref "C67F") (pin "2") (pinfunction "2_2") (pintype "passive"))
      (node (ref "C68F") (pin "2") (pinfunction "2_2") (pintype "passive"))
      (node (ref "C69F") (pin "2") (pinfunction "2_2") (pintype "passive"))
      (node (ref "C70F") (pin "1") (pinfunction "1_1") (pintype "passive"))
      (node (ref "C71F") (pin "2") (pinfunction "2_2") (pintype "passive"))
      (node (ref "C72F") (pin "2") (pinfunction "2_2") (pintype "passive"))
      (node (ref "C73F") (pin "2") (pinfunction "2_2") (pintype "passive"))
      (node (ref "C74F") (pin "2") (pinfunction "2_2") (pintype "passive"))
      (node (ref "C76F") (pin "2") (pinfunction "2_2") (pintype "passive"))
      (node (ref "C77F") (pin "2") (pinfunction "2_2") (pintype "passive"))
      (node (ref "C78F") (pin "2") (pinfunction "2_2") (pintype "passive"))
      (node (ref "C79F") (pin "2") (pinfunction "2_2") (pintype "passive"))
      (node (ref "C80F") (pin "2") (pinfunction "2_2") (pintype "passive"))
      (node (ref "C81F") (pin "2") (pinfunction "2_2") (pintype "passive"))
      (node (ref "C82F") (pin "1") (pinfunction "1_1") (pintype "passive"))
      (node (ref "C83F") (pin "2") (pinfunction "2_2") (pintype "passive"))
      (node (ref "C84F") (pin "2") (pinfunction "2_2") (pintype "passive"))
      (node (ref "C85F") (pin "2") (pinfunction "2_2") (pintype "passive"))
      (node (ref "C86F") (pin "2") (pinfunction "2_2") (pintype "passive"))
      (node (ref "C87F") (pin "2") (pinfunction "2_2") (pintype "passive"))
      (node (ref "C88F") (pin "2") (pinfunction "2_2") (pintype "passive"))
      (node (ref "C89F") (pin "2") (pinfunction "2_2") (pintype "passive"))
      (node (ref "C90F") (pin "2") (pinfunction "2_2") (pintype "passive"))
      (node (ref "C91F") (pin "2") (pinfunction "2_2") (pintype "passive"))
      (node (ref "C92F") (pin "2") (pinfunction "2_2") (pintype "passive"))
      (node (ref "C93F") (pin "2") (pinfunction "2_2") (pintype "passive"))
      (node (ref "C94F") (pin "1") (pinfunction "1_1") (pintype "passive"))
      (node (ref "D11F") (pin "1") (pinfunction "A_1") (pintype "passive"))
      (node (ref "JP10F") (pin "A11") (pinfunction "A11_A11") (pintype "passive"))
      (node (ref "JP10F") (pin "A13") (pinfunction "A13_A13") (pintype "passive"))
      (node (ref "JP10F") (pin "A18") (pinfunction "A18_A18") (pintype "passive"))
      (node (ref "JP10F") (pin "A21") (pinfunction "A21_A21") (pintype "passive"))
      (node (ref "JP10F") (pin "A24") (pinfunction "A24_A24") (pintype "passive"))
      (node (ref "JP10F") (pin "A28") (pinfunction "A28_A28") (pintype "passive"))
      (node (ref "JP10F") (pin "A31") (pinfunction "A31_A31") (pintype "passive"))
      (node (ref "JP10F") (pin "B13") (pinfunction "B13_B13") (pintype "passive"))
      (node (ref "JP10F") (pin "B17") (pinfunction "B17_B17") (pintype "passive"))
      (node (ref "JP10F") (pin "B20") (pinfunction "B20_B20") (pintype "passive"))
      (node (ref "JP10F") (pin "B23") (pinfunction "B23_B23") (pintype "passive"))
      (node (ref "JP10F") (pin "B30") (pinfunction "B30_B30") (pintype "passive"))
      (node (ref "JP10F") (pin "B33") (pinfunction "B33_B33") (pintype "passive"))
      (node (ref "JP10F") (pin "B7") (pinfunction "B7_B7") (pintype "passive"))
      (node (ref "JP10F") (pin "GND1") (pinfunction "GND1_GND1") (pintype "passive"))
      (node (ref "JP10F") (pin "GND2") (pinfunction "GND2_GND2") (pintype "passive"))
      (node (ref "JP10F") (pin "GND3") (pinfunction "GND3_GND3") (pintype "passive"))
      (node (ref "JP10F") (pin "GND4") (pinfunction "GND4_GND4") (pintype "passive"))
      (node (ref "JP10F") (pin "GND5") (pinfunction "GND5_GND5") (pintype "passive"))
      (node (ref "JP10F") (pin "GND6") (pinfunction "GND6_GND6") (pintype "passive"))
      (node (ref "JP10F") (pin "GND7") (pinfunction "GND7_GND7") (pintype "passive"))
      (node (ref "JP10F") (pin "GND8") (pinfunction "GND8_GND8") (pintype "passive"))
      (node (ref "P10F") (pin "6") (pinfunction "6_6") (pintype "passive"))
      (node (ref "Q10F") (pin "2") (pinfunction "S_2") (pintype "passive"))
      (node (ref "Q12F") (pin "2") (pinfunction "S_2") (pintype "passive"))
      (node (ref "R12F") (pin "1") (pinfunction "1_1") (pintype "passive"))
      (node (ref "R15F") (pin "1") (pinfunction "1_1") (pintype "passive"))
      (node (ref "R17F") (pin "1") (pinfunction "1_1") (pintype "passive"))
      (node (ref "R18F") (pin "2") (pinfunction "2_2") (pintype "passive"))
      (node (ref "R23F") (pin "1") (pinfunction "1_1") (pintype "passive"))
      (node (ref "R24F") (pin "2") (pinfunction "2_2") (pintype "passive"))
      (node (ref "R27F") (pin "1") (pinfunction "1_1") (pintype "passive"))
      (node (ref "R28F") (pin "1") (pinfunction "1_1") (pintype "passive"))
      (node (ref "R29F") (pin "2") (pinfunction "2_2") (pintype "passive"))
      (node (ref "R32F") (pin "1") (pinfunction "1_1") (pintype "passive"))
      (node (ref "R33F") (pin "1") (pinfunction "1_1") (pintype "passive"))
      (node (ref "R34F") (pin "1") (pinfunction "1_1") (pintype "passive"))
      (node (ref "U10F") (pin "2") (pinfunction "GND_2") (pintype "power_in"))
      (node (ref "U10F") (pin "7") (pinfunction "GND_7") (pintype "power_in"))
      (node (ref "U11F") (pin "2") (pinfunction "GND_2") (pintype "power_in"))
      (node (ref "U11F") (pin "3") (pinfunction "A_3") (pintype "input"))
      (node (ref "U12F") (pin "A9") (pinfunction "VSS_A9") (pintype "power_in"))
      (node (ref "U12F") (pin "B1") (pinfunction "VSSQ_B1") (pintype "power_in"))
      (node (ref "U12F") (pin "B3") (pinfunction "VSS_B3") (pintype "power_in"))
      (node (ref "U12F") (pin "B9") (pinfunction "VSSQ_B9") (pintype "power_in"))
      (node (ref "U12F") (pin "D1") (pinfunction "VSSQ_D1") (pintype "power_in"))
      (node (ref "U12F") (pin "D8") (pinfunction "VSSQ_D8") (pintype "power_in"))
      (node (ref "U12F") (pin "E1") (pinfunction "VSS_E1") (pintype "power_in"))
      (node (ref "U12F") (pin "E2") (pinfunction "VSSQ_E2") (pintype "power_in"))
      (node (ref "U12F") (pin "E8") (pinfunction "VSSQ_E8") (pintype "power_in"))
      (node (ref "U12F") (pin "F9") (pinfunction "VSSQ_F9") (pintype "power_in"))
      (node (ref "U12F") (pin "G1") (pinfunction "VSSQ_G1") (pintype "power_in"))
      (node (ref "U12F") (pin "G8") (pinfunction "VSS_G8") (pintype "power_in"))
      (node (ref "U12F") (pin "G9") (pinfunction "VSSQ_G9") (pintype "power_in"))
      (node (ref "U12F") (pin "J2") (pinfunction "VSS_J2") (pintype "power_in"))
      (node (ref "U12F") (pin "J8") (pinfunction "VSS_J8") (pintype "power_in"))
      (node (ref "U12F") (pin "L2") (pinfunction "CS#_L2") (pintype "input"))
      (node (ref "U12F") (pin "M1") (pinfunction "VSS_M1") (pintype "power_in"))
      (node (ref "U12F") (pin "M9") (pinfunction "VSS_M9") (pintype "power_in"))
      (node (ref "U12F") (pin "P1") (pinfunction "VSS_P1") (pintype "power_in"))
      (node (ref "U12F") (pin "P9") (pinfunction "VSS_P9") (pintype "power_in"))
      (node (ref "U12F") (pin "T1") (pinfunction "VSS_T1") (pintype "power_in"))
      (node (ref "U12F") (pin "T9") (pinfunction "VSS_T9") (pintype "power_in"))
      (node (ref "U800") (pin "A1") (pinfunction "GND_A1") (pintype "power_in"))
      (node (ref "U800") (pin "A18") (pinfunction "GND_A18") (pintype "power_in"))
      (node (ref "U800") (pin "B13") (pinfunction "GND_B13") (pintype "power_in"))
      (node (ref "U800") (pin "B7") (pinfunction "GND_B7") (pintype "power_in"))
      (node (ref "U800") (pin "C16") (pinfunction "GND_C16") (pintype "power_in"))
      (node (ref "U800") (pin "C3") (pinfunction "GND_C3") (pintype "power_in"))
      (node (ref "U800") (pin "D10") (pinfunction "GND_D10") (pintype "power_in"))
      (node (ref "U800") (pin "D5") (pinfunction "GND_D5") (pintype "power_in"))
      (node (ref "U800") (pin "E15") (pinfunction "GND_E15") (pintype "power_in"))
      (node (ref "U800") (pin "G12") (pinfunction "GND_G12") (pintype "power_in"))
      (node (ref "U800") (pin "G17") (pinfunction "GND_G17") (pintype "power_in"))
      (node (ref "U800") (pin "G2") (pinfunction "GND_G2") (pintype "power_in"))
      (node (ref "U800") (pin "G5") (pinfunction "GND_G5") (pintype "power_in"))
      (node (ref "U800") (pin "H10") (pinfunction "GND_H10") (pintype "power_in"))
      (node (ref "U800") (pin "H8") (pinfunction "GND_H8") (pintype "power_in"))
      (node (ref "U800") (pin "J11") (pinfunction "GND_J11") (pintype "power_in"))
      (node (ref "U800") (pin "J15") (pinfunction "GND_J15") (pintype "power_in"))
      (node (ref "U800") (pin "J4") (pinfunction "GND_J4") (pintype "power_in"))
      (node (ref "U800") (pin "J9") (pinfunction "GND_J9") (pintype "power_in"))
      (node (ref "U800") (pin "K10") (pinfunction "GND_K10") (pintype "power_in"))
      (node (ref "U800") (pin "K8") (pinfunction "GND_K8") (pintype "power_in"))
      (node (ref "U800") (pin "L11") (pinfunction "GND_L11") (pintype "power_in"))
      (node (ref "U800") (pin "L9") (pinfunction "GND_L9") (pintype "power_in"))
      (node (ref "U800") (pin "M17") (pinfunction "GND_M17") (pintype "power_in"))
      (node (ref "U800") (pin "M2") (pinfunction "GND_M2") (pintype "power_in"))
      (node (ref "U800") (pin "M6") (pinfunction "GND_M6") (pintype "power_in"))
      (node (ref "U800") (pin "N13") (pinfunction "GND_N13") (pintype "power_in"))
      (node (ref "U800") (pin "R1") (pinfunction "GND_R1") (pintype "power_in"))
      (node (ref "U800") (pin "R14") (pinfunction "GND_R14") (pintype "power_in"))
      (node (ref "U800") (pin "R18") (pinfunction "GND_R18") (pintype "power_in"))
      (node (ref "U800") (pin "R4") (pinfunction "GND_R4") (pintype "power_in"))
      (node (ref "U800") (pin "R9") (pinfunction "GND_R9") (pintype "power_in"))
      (node (ref "U800") (pin "T16") (pinfunction "GND_T16") (pintype "power_in"))
      (node (ref "U800") (pin "U12") (pinfunction "GND_U12") (pintype "power_in"))
      (node (ref "U800") (pin "U6") (pinfunction "GND_U6") (pintype "power_in"))
      (node (ref "U800") (pin "V1") (pinfunction "GND_V1") (pintype "power_in"))
      (node (ref "U800") (pin "V18") (pinfunction "GND_V18") (pintype "power_in"))
    )
    (net (code "191") (name "Net-(D11F-K)") (class "Default")
      (node (ref "D11F") (pin "2") (pinfunction "K_2") (pintype "passive"))
      (node (ref "L10F") (pin "1") (pinfunction "1_1") (pintype "passive"))
      (node (ref "U10F") (pin "3") (pinfunction "SW_3") (pintype "passive"))
    )
    (net (code "192") (name "Net-(D12F-K)") (class "Default")
      (node (ref "D12F") (pin "2") (pinfunction "K_2") (pintype "passive"))
      (node (ref "R27F") (pin "2") (pinfunction "2_2") (pintype "passive"))
    )
    (net (code "193") (name "Net-(Q10F-G)") (class "Default")
      (node (ref "Q10F") (pin "1") (pinfunction "G_1") (pintype "passive"))
      (node (ref "R26F") (pin "1") (pinfunction "1_1") (pintype "passive"))
      (node (ref "U11F") (pin "4") (pinfunction "Y_4") (pintype "output"))
    )
    (net (code "194") (name "Net-(Q11F-G)") (class "Default")
      (node (ref "C95F") (pin "2") (pinfunction "2_2") (pintype "passive"))
      (node (ref "Q11F") (pin "4") (pinfunction "G_4") (pintype "passive"))
      (node (ref "R30F") (pin "1") (pinfunction "1_1") (pintype "passive"))
      (node (ref "R35F") (pin "1") (pinfunction "1_1") (pintype "passive"))
    )
    (net (code "195") (name "Net-(Q12F-D)") (class "Default")
      (node (ref "Q12F") (pin "3") (pinfunction "D_3") (pintype "passive"))
      (node (ref "R35F") (pin "2") (pinfunction "2_2") (pintype "passive"))
    )
    (net (code "196") (name "Net-(U10F-EN)") (class "Default")
      (node (ref "R20F") (pin "1") (pinfunction "1_1") (pintype "passive"))
      (node (ref "U10F") (pin "6") (pinfunction "EN_6") (pintype "input"))
    )
    (net (code "197") (name "Net-(U10F-FB)") (class "Default")
      (node (ref "R18F") (pin "1") (pinfunction "1_1") (pintype "passive"))
      (node (ref "R19F") (pin "2") (pinfunction "2_2") (pintype "passive"))
      (node (ref "U10F") (pin "1") (pinfunction "FB_1") (pintype "passive"))
    )
    (net (code "198") (name "P0.75V_REFDDR") (class "Default")
      (node (ref "R10F") (pin "1") (pinfunction "1_1") (pintype "passive"))
    )
    (net (code "199") (name "P1.2V") (class "Default")
      (node (ref "C51F") (pin "1") (pinfunction "1_1") (pintype "passive"))
      (node (ref "C52F") (pin "1") (pinfunction "1_1") (pintype "passive"))
      (node (ref "C53F") (pin "1") (pinfunction "1_1") (pintype "passive"))
      (node (ref "C54F") (pin "1") (pinfunction "1_1") (pintype "passive"))
      (node (ref "C55F") (pin "1") (pinfunction "1_1") (pintype "passive"))
      (node (ref "C56F") (pin "1") (pinfunction "1_1") (pintype "passive"))
      (node (ref "C57F") (pin "1") (pinfunction "1_1") (pintype "passive"))
      (node (ref "C58F") (pin "1") (pinfunction "1_1") (pintype "passive"))
      (node (ref "C59F") (pin "1") (pinfunction "1_1") (pintype "passive"))
      (node (ref "C60F") (pin "2") (pinfunction "2_2") (pintype "passive"))
      (node (ref "C61F") (pin "1") (pinfunction "1_1") (pintype "passive"))
      (node (ref "C62F") (pin "1") (pinfunction "1_1") (pintype "passive"))
      (node (ref "C63F") (pin "1") (pinfunction "1_1") (pintype "passive"))
      (node (ref "L10F") (pin "2") (pinfunction "2_2") (pintype "passive"))
      (node (ref "R19F") (pin "1") (pinfunction "1_1") (pintype "passive"))
      (node (ref "U800") (pin "G7") (pinfunction "VCCINT_G7") (pintype "power_in"))
      (node (ref "U800") (pin "H11") (pinfunction "VCCINT_H11") (pintype "power_in"))
      (node (ref "U800") (pin "H9") (pinfunction "VCCINT_H9") (pintype "power_in"))
      (node (ref "U800") (pin "J10") (pinfunction "VCCINT_J10") (pintype "power_in"))
      (node (ref "U800") (pin "J8") (pinfunction "VCCINT_J8") (pintype "power_in"))
      (node (ref "U800") (pin "K11") (pinfunction "VCCINT_K11") (pintype "power_in"))
      (node (ref "U800") (pin "K9") (pinfunction "VCCINT_K9") (pintype "power_in"))
      (node (ref "U800") (pin "L10") (pinfunction "VCCINT_L10") (pintype "power_in"))
      (node (ref "U800") (pin "L8") (pinfunction "VCCINT_L8") (pintype "power_in"))
      (node (ref "U800") (pin "M12") (pinfunction "VCCINT_M12") (pintype "power_in"))
      (node (ref "U800") (pin "M7") (pinfunction "VCCINT_M7") (pintype "power_in"))
    )
    (net (code "200") (name "P1.5V_DDR_SW3") (class "Default")
      (node (ref "C15F") (pin "1") (pinfunction "1_1") (pintype "passive"))
      (node (ref "C16F") (pin "1") (pinfunction "1_1") (pintype "passive"))
      (node (ref "C17F") (pin "1") (pinfunction "1_1") (pintype "passive"))
      (node (ref "C18F") (pin "1") (pinfunction "1_1") (pintype "passive"))
      (node (ref "C19F") (pin "1") (pinfunction "1_1") (pintype "passive"))
      (node (ref "C20F") (pin "2") (pinfunction "2_2") (pintype "passive"))
      (node (ref "C21F") (pin "1") (pinfunction "1_1") (pintype "passive"))
      (node (ref "C44F") (pin "1") (pinfunction "1_1") (pintype "passive"))
      (node (ref "C70F") (pin "2") (pinfunction "2_2") (pintype "passive"))
      (node (ref "C71F") (pin "1") (pinfunction "1_1") (pintype "passive"))
      (node (ref "C72F") (pin "1") (pinfunction "1_1") (pintype "passive"))
      (node (ref "C73F") (pin "1") (pinfunction "1_1") (pintype "passive"))
      (node (ref "C74F") (pin "1") (pinfunction "1_1") (pintype "passive"))
      (node (ref "C76F") (pin "1") (pinfunction "1_1") (pintype "passive"))
      (node (ref "C77F") (pin "1") (pinfunction "1_1") (pintype "passive"))
      (node (ref "C78F") (pin "1") (pinfunction "1_1") (pintype "passive"))
      (node (ref "C79F") (pin "1") (pinfunction "1_1") (pintype "passive"))
      (node (ref "C80F") (pin "1") (pinfunction "1_1") (pintype "passive"))
      (node (ref "C81F") (pin "1") (pinfunction "1_1") (pintype "passive"))
      (node (ref "C84F") (pin "1") (pinfunction "1_1") (pintype "passive"))
      (node (ref "C85F") (pin "1") (pinfunction "1_1") (pintype "passive"))
      (node (ref "C86F") (pin "1") (pinfunction "1_1") (pintype "passive"))
      (node (ref "C87F") (pin "1") (pinfunction "1_1") (pintype "passive"))
      (node (ref "C88F") (pin "1") (pinfunction "1_1") (pintype "passive"))
      (node (ref "C89F") (pin "1") (pinfunction "1_1") (pintype "passive"))
      (node (ref "C90F") (pin "1") (pinfunction "1_1") (pintype "passive"))
      (node (ref "C91F") (pin "1") (pinfunction "1_1") (pintype "passive"))
      (node (ref "R11F") (pin "1") (pinfunction "1_1") (pintype "passive"))
      (node (ref "U12F") (pin "A1") (pinfunction "VDDQ_A1") (pintype "power_in"))
      (node (ref "U12F") (pin "A8") (pinfunction "VDDQ_A8") (pintype "power_in"))
      (node (ref "U12F") (pin "B2") (pinfunction "VDD_B2") (pintype "power_in"))
      (node (ref "U12F") (pin "C1") (pinfunction "VDDQ_C1") (pintype "power_in"))
      (node (ref "U12F") (pin "C9") (pinfunction "VDDQ_C9") (pintype "power_in"))
      (node (ref "U12F") (pin "D2") (pinfunction "VDDQ_D2") (pintype "power_in"))
      (node (ref "U12F") (pin "D9") (pinfunction "VDD_D9") (pintype "power_in"))
      (node (ref "U12F") (pin "E9") (pinfunction "VDDQ_E9") (pintype "power_in"))
      (node (ref "U12F") (pin "F1") (pinfunction "VDDQ_F1") (pintype "power_in"))
      (node (ref "U12F") (pin "G7") (pinfunction "VDD_G7") (pintype "power_in"))
      (node (ref "U12F") (pin "H2") (pinfunction "VDDQ_H2") (pintype "power_in"))
      (node (ref "U12F") (pin "H9") (pinfunction "VDDQ_H9") (pintype "power_in"))
      (node (ref "U12F") (pin "K2") (pinfunction "VDD_K2") (pintype "power_in"))
      (node (ref "U12F") (pin "K8") (pinfunction "VDD_K8") (pintype "power_in"))
      (node (ref "U12F") (pin "N1") (pinfunction "VDD_N1") (pintype "power_in"))
      (node (ref "U12F") (pin "N9") (pinfunction "VDD_N9") (pintype "power_in"))
      (node (ref "U12F") (pin "R1") (pinfunction "VDD_R1") (pintype "power_in"))
      (node (ref "U12F") (pin "R9") (pinfunction "VDD_R9") (pintype "power_in"))
      (node (ref "U800") (pin "E17") (pinfunction "VCCO_1_E17") (pintype "power_in"))
      (node (ref "U800") (pin "G15") (pinfunction "VCCO_1_G15") (pintype "power_in"))
      (node (ref "U800") (pin "J14") (pinfunction "VCCO_1_J14") (pintype "power_in"))
      (node (ref "U800") (pin "J17") (pinfunction "VCCO_1_J17") (pintype "power_in"))
      (node (ref "U800") (pin "M15") (pinfunction "VCCO_1_M15") (pintype "power_in"))
      (node (ref "U800") (pin "R17") (pinfunction "VCCO_1_R17") (pintype "power_in"))
    )
    (net (code "201") (name "P3.3V_DELAYED") (class "Default")
      (node (ref "C10F") (pin "1") (pinfunction "1_1") (pintype "passive"))
      (node (ref "C11F") (pin "1") (pinfunction "1_1") (pintype "passive"))
      (node (ref "C12F") (pin "1") (pinfunction "1_1") (pintype "passive"))
      (node (ref "C13F") (pin "1") (pinfunction "1_1") (pintype "passive"))
      (node (ref "C14F") (pin "1") (pinfunction "1_1") (pintype "passive"))
      (node (ref "C22F") (pin "1") (pinfunction "1_1") (pintype "passive"))
      (node (ref "C23F") (pin "1") (pinfunction "1_1") (pintype "passive"))
      (node (ref "C24F") (pin "1") (pinfunction "1_1") (pintype "passive"))
      (node (ref "C25F") (pin "1") (pinfunction "1_1") (pintype "passive"))
      (node (ref "C26F") (pin "1") (pinfunction "1_1") (pintype "passive"))
      (node (ref "C27F") (pin "1") (pinfunction "1_1") (pintype "passive"))
      (node (ref "C28F") (pin "1") (pinfunction "1_1") (pintype "passive"))
      (node (ref "C29F") (pin "1") (pinfunction "1_1") (pintype "passive"))
      (node (ref "C30F") (pin "2") (pinfunction "2_2") (pintype "passive"))
      (node (ref "C31F") (pin "1") (pinfunction "1_1") (pintype "passive"))
      (node (ref "C32F") (pin "1") (pinfunction "1_1") (pintype "passive"))
      (node (ref "C33F") (pin "1") (pinfunction "1_1") (pintype "passive"))
      (node (ref "C34F") (pin "1") (pinfunction "1_1") (pintype "passive"))
      (node (ref "C35F") (pin "1") (pinfunction "1_1") (pintype "passive"))
      (node (ref "C36F") (pin "1") (pinfunction "1_1") (pintype "passive"))
      (node (ref "C37F") (pin "1") (pinfunction "1_1") (pintype "passive"))
      (node (ref "C38F") (pin "1") (pinfunction "1_1") (pintype "passive"))
      (node (ref "C39F") (pin "1") (pinfunction "1_1") (pintype "passive"))
      (node (ref "C40F") (pin "2") (pinfunction "2_2") (pintype "passive"))
      (node (ref "C41F") (pin "1") (pinfunction "1_1") (pintype "passive"))
      (node (ref "C42F") (pin "1") (pinfunction "1_1") (pintype "passive"))
      (node (ref "C43F") (pin "1") (pinfunction "1_1") (pintype "passive"))
      (node (ref "C45F") (pin "1") (pinfunction "1_1") (pintype "passive"))
      (node (ref "C46F") (pin "1") (pinfunction "1_1") (pintype "passive"))
      (node (ref "C47F") (pin "1") (pinfunction "1_1") (pintype "passive"))
      (node (ref "C48F") (pin "1") (pinfunction "1_1") (pintype "passive"))
      (node (ref "C49F") (pin "2") (pinfunction "2_2") (pintype "passive"))
      (node (ref "C50F") (pin "1") (pinfunction "1_1") (pintype "passive"))
      (node (ref "C66F") (pin "1") (pinfunction "1_1") (pintype "passive"))
      (node (ref "P10F") (pin "1") (pinfunction "1_1") (pintype "passive"))
      (node (ref "R13F") (pin "2") (pinfunction "2_2") (pintype "passive"))
      (node (ref "R14F") (pin "1") (pinfunction "1_1") (pintype "passive"))
      (node (ref "R16F") (pin "1") (pinfunction "1_1") (pintype "passive"))
      (node (ref "R21F") (pin "1") (pinfunction "1_1") (pintype "passive"))
      (node (ref "R22F") (pin "2") (pinfunction "2_2") (pintype "passive"))
      (node (ref "R25F") (pin "2") (pinfunction "2_2") (pintype "passive"))
      (node (ref "R36F") (pin "1") (pinfunction "1_1") (pintype "passive"))
      (node (ref "U11F") (pin "5") (pinfunction "Vcc_5") (pintype "power_in"))
      (node (ref "U800") (pin "B1") (pinfunction "VCCAUX_B1") (pintype "power_in"))
      (node (ref "U800") (pin "B10") (pinfunction "VCCO_0_B10") (pintype "power_in"))
      (node (ref "U800") (pin "B15") (pinfunction "VCCO_0_B15") (pintype "power_in"))
      (node (ref "U800") (pin "B17") (pinfunction "VCCAUX_B17") (pintype "power_in"))
      (node (ref "U800") (pin "B5") (pinfunction "VCCO_0_B5") (pintype "power_in"))
      (node (ref "U800") (pin "D13") (pinfunction "VCCO_0_D13") (pintype "power_in"))
      (node (ref "U800") (pin "D7") (pinfunction "VCCO_0_D7") (pintype "power_in"))
      (node (ref "U800") (pin "E10") (pinfunction "VCCO_0_E10") (pintype "power_in"))
      (node (ref "U800") (pin "E14") (pinfunction "VCCAUX_E14") (pintype "power_in"))
      (node (ref "U800") (pin "E2") (pinfunction "VCCO_3_E2") (pintype "power_in"))
      (node (ref "U800") (pin "E5") (pinfunction "VCCAUX_E5") (pintype "power_in"))
      (node (ref "U800") (pin "E9") (pinfunction "VCCAUX_E9") (pintype "power_in"))
      (node (ref "U800") (pin "G10") (pinfunction "VCCAUX_G10") (pintype "power_in"))
      (node (ref "U800") (pin "G4") (pinfunction "VCCO_3_G4") (pintype "power_in"))
      (node (ref "U800") (pin "J12") (pinfunction "VCCAUX_J12") (pintype "power_in"))
      (node (ref "U800") (pin "J2") (pinfunction "VCCO_3_J2") (pintype "power_in"))
      (node (ref "U800") (pin "J5") (pinfunction "VCCO_3_J5") (pintype "power_in"))
      (node (ref "U800") (pin "K7") (pinfunction "VCCAUX_K7") (pintype "power_in"))
      (node (ref "U800") (pin "M4") (pinfunction "VCCO_3_M4") (pintype "power_in"))
      (node (ref "U800") (pin "M9") (pinfunction "VCCAUX_M9") (pintype "power_in"))
      (node (ref "U800") (pin "P10") (pinfunction "VCCAUX_P10") (pintype "power_in"))
      (node (ref "U800") (pin "P14") (pinfunction "VCCAUX_P14") (pintype "power_in"))
      (node (ref "U800") (pin "P5") (pinfunction "VCCAUX_P5") (pintype "power_in"))
      (node (ref "U800") (pin "P9") (pinfunction "VCCO_2_P9") (pintype "power_in"))
      (node (ref "U800") (pin "R12") (pinfunction "VCCO_2_R12") (pintype "power_in"))
      (node (ref "U800") (pin "R2") (pinfunction "VCCO_3_R2") (pintype "power_in"))
      (node (ref "U800") (pin "R6") (pinfunction "VCCO_2_R6") (pintype "power_in"))
      (node (ref "U800") (pin "U14") (pinfunction "VCCO_2_U14") (pintype "power_in"))
      (node (ref "U800") (pin "U4") (pinfunction "VCCO_2_U4") (pintype "power_in"))
      (node (ref "U800") (pin "U9") (pinfunction "VCCO_2_U9") (pintype "power_in"))
    )
    (net (code "202") (name "P5.0V_DELAYED") (class "Default")
      (node (ref "C65F") (pin "2") (pinfunction "2_2") (pintype "passive"))
      (node (ref "C95F") (pin "1") (pinfunction "1_1") (pintype "passive"))
      (node (ref "Q11F") (pin "1") (pinfunction "S_1") (pintype "passive"))
      (node (ref "Q11F") (pin "2") (pinfunction "S_2") (pintype "passive"))
      (node (ref "Q11F") (pin "3") (pinfunction "S_3") (pintype "passive"))
      (node (ref "R20F") (pin "2") (pinfunction "2_2") (pintype "passive"))
      (node (ref "R30F") (pin "2") (pinfunction "2_2") (pintype "passive"))
      (node (ref "U10F") (pin "4") (pinfunction "VIND_4") (pintype "power_in"))
      (node (ref "U10F") (pin "5") (pinfunction "VINA_5") (pintype "power_in"))
    )
    (net (code "203") (name "unconnected-(U800A-IO_L2P_0-PadB2)") (class "Default")
      (node (ref "U800") (pin "B2") (pinfunction "IO_L2P_0_B2") (pintype "bidirectional"))
    )
    (net (code "204") (name "unconnected-(U800A-IO_L3N_0-PadC6)") (class "Default")
      (node (ref "U800") (pin "C6") (pinfunction "IO_L3N_0_C6") (pintype "bidirectional"))
    )
    (net (code "205") (name "unconnected-(U800A-IO_L3P_0-PadD6)") (class "Default")
      (node (ref "U800") (pin "D6") (pinfunction "IO_L3P_0_D6") (pintype "bidirectional"))
    )
    (net (code "206") (name "unconnected-(U800B-IO_L61N_1-PadM13)") (class "Default")
      (node (ref "U800") (pin "M13") (pinfunction "IO_L61N_1_M13") (pintype "bidirectional"))
    )
    (net (code "207") (name "unconnected-(U800B-IO_L61P_1-PadL14)") (class "Default")
      (node (ref "U800") (pin "L14") (pinfunction "IO_L61P_1_L14") (pintype "bidirectional"))
    )
    (net (code "208") (name "unconnected-(U800B-IO_L74N_DOUT_BUSY_1-PadP16)") (class "Default")
      (node (ref "U800") (pin "P16") (pinfunction "IO_L74N_DOUT_BUSY_1_P16") (pintype "bidirectional"))
    )
    (net (code "209") (name "unconnected-(U800B-IO_L74P_AWAKE_1-PadP15)") (class "Default")
      (node (ref "U800") (pin "P15") (pinfunction "IO_L74P_AWAKE_1_P15") (pintype "bidirectional"))
    )
    (net (code "210") (name "unconnected-(U800C-IO_L3N_MOSI_CSI_B_MISO0_2-PadT13)") (class "Default")
      (node (ref "U800") (pin "T13") (pinfunction "IO_L3N_MOSI_CSI_B_MISO0_2_T13") (pintype "bidirectional"))
    )
    (net (code "211") (name "unconnected-(U800C-IO_L13N_D10_2-PadP12)") (class "Default")
      (node (ref "U800") (pin "P12") (pinfunction "IO_L13N_D10_2_P12") (pintype "bidirectional"))
    )
    (net (code "212") (name "unconnected-(U800C-IO_L65N_CSO_B_2-PadV3)") (class "Default")
      (node (ref "U800") (pin "V3") (pinfunction "IO_L65N_CSO_B_2_V3") (pintype "bidirectional"))
    )
    (net (code "213") (name "unconnected-(U800D-IO_L47P_M3A0_3-PadJ7)") (class "Default")
      (node (ref "U800") (pin "J7") (pinfunction "IO_L47P_M3A0_3_J7") (pintype "bidirectional"))
    )
    (net (code "214") (name "unconnected-(U800D-IO_L49N_M3A2_3-PadH5)") (class "Default")
      (node (ref "U800") (pin "H5") (pinfunction "IO_L49N_M3A2_3_H5") (pintype "bidirectional"))
    )
    (net (code "215") (name "unconnected-(U800D-IO_L50N_M3BA2_3-PadE1)") (class "Default")
      (node (ref "U800") (pin "E1") (pinfunction "IO_L50N_M3BA2_3_E1") (pintype "bidirectional"))
    )
    (net (code "216") (name "unconnected-(U800D-IO_L51N_M3A4_3-PadF3)") (class "Default")
      (node (ref "U800") (pin "F3") (pinfunction "IO_L51N_M3A4_3_F3") (pintype "bidirectional"))
    )
    (net (code "217") (name "unconnected-(U800D-IO_L51P_M3A10_3-PadF4)") (class "Default")
      (node (ref "U800") (pin "F4") (pinfunction "IO_L51P_M3A10_3_F4") (pintype "bidirectional"))
    )
    (net (code "218") (name "unconnected-(U800D-IO_L53N_M3A12_3-PadG6)") (class "Default")
      (node (ref "U800") (pin "G6") (pinfunction "IO_L53N_M3A12_3_G6") (pintype "bidirectional"))
    )
    (net (code "219") (name "unconnected-(U800D-IO_L54P_M3RESET_3-PadE4)") (class "Default")
      (node (ref "U800") (pin "E4") (pinfunction "IO_L54P_M3RESET_3_E4") (pintype "bidirectional"))
    )
    (net (code "220") (name "unconnected-(U800D-IO_L55N_M3A14_3-PadF5)") (class "Default")
      (node (ref "U800") (pin "F5") (pinfunction "IO_L55N_M3A14_3_F5") (pintype "bidirectional"))
    )
    (net (code "221") (name "unconnected-(U800D-IO_L55P_M3A13_3-PadF6)") (class "Default")
      (node (ref "U800") (pin "F6") (pinfunction "IO_L55P_M3A13_3_F6") (pintype "bidirectional"))
    )
    (net (code "222") (name "unconnected-(U800E-CMPCS_B_2-PadP13)") (class "Default")
      (node (ref "U800") (pin "P13") (pinfunction "CMPCS_B_2_P13") (pintype "input+no_connect"))
    )
    (net (code "223") (name "unconnected-(U800H-NC-PadA13)") (class "Default")
      (node (ref "U800") (pin "A13") (pinfunction "NC_A13") (pintype "passive"))
    )
    (net (code "224") (name "unconnected-(U800H-NC-PadC12)") (class "Default")
      (node (ref "U800") (pin "C12") (pinfunction "NC_C12") (pintype "passive"))
    )
    (net (code "225") (name "unconnected-(U800H-NC-PadC13)") (class "Default")
      (node (ref "U800") (pin "C13") (pinfunction "NC_C13") (pintype "passive"))
    )
    (net (code "226") (name "unconnected-(U800H-NC-PadD12)") (class "Default")
      (node (ref "U800") (pin "D12") (pinfunction "NC_D12") (pintype "passive"))
    )
    (net (code "227") (name "unconnected-(U800H-NC-PadE6)") (class "Default")
      (node (ref "U800") (pin "E6") (pinfunction "NC_E6") (pintype "passive"))
    )
    (net (code "228") (name "unconnected-(U800H-NC-PadE7)") (class "Default")
      (node (ref "U800") (pin "E7") (pinfunction "NC_E7") (pintype "passive"))
    )
    (net (code "229") (name "unconnected-(U800H-NC-PadE8)") (class "Default")
      (node (ref "U800") (pin "E8") (pinfunction "NC_E8") (pintype "passive"))
    )
    (net (code "230") (name "unconnected-(U800H-NC-PadE11)") (class "Default")
      (node (ref "U800") (pin "E11") (pinfunction "NC_E11") (pintype "passive"))
    )
    (net (code "231") (name "unconnected-(U800H-NC-PadE12)") (class "Default")
      (node (ref "U800") (pin "E12") (pinfunction "NC_E12") (pintype "passive"))
    )
    (net (code "232") (name "unconnected-(U800H-NC-PadF7)") (class "Default")
      (node (ref "U800") (pin "F7") (pinfunction "NC_F7") (pintype "passive"))
    )
    (net (code "233") (name "unconnected-(U800H-NC-PadF8)") (class "Default")
      (node (ref "U800") (pin "F8") (pinfunction "NC_F8") (pintype "passive"))
    )
    (net (code "234") (name "unconnected-(U800H-NC-PadF10)") (class "Default")
      (node (ref "U800") (pin "F10") (pinfunction "NC_F10") (pintype "passive"))
    )
    (net (code "235") (name "unconnected-(U800H-NC-PadF11)") (class "Default")
      (node (ref "U800") (pin "F11") (pinfunction "NC_F11") (pintype "passive"))
    )
    (net (code "236") (name "unconnected-(U800H-NC-PadF12)") (class "Default")
      (node (ref "U800") (pin "F12") (pinfunction "NC_F12") (pintype "passive"))
    )
    (net (code "237") (name "unconnected-(U800H-NC-PadG8)") (class "Default")
      (node (ref "U800") (pin "G8") (pinfunction "NC_G8") (pintype "passive"))
    )
    (net (code "238") (name "unconnected-(U800H-NC-PadG11)") (class "Default")
      (node (ref "U800") (pin "G11") (pinfunction "NC_G11") (pintype "passive"))
    )
    (net (code "239") (name "unconnected-(U800H-NC-PadM8)") (class "Default")
      (node (ref "U800") (pin "M8") (pinfunction "NC_M8") (pintype "passive"))
    )
    (net (code "240") (name "unconnected-(U800H-NC-PadM10)") (class "Default")
      (node (ref "U800") (pin "M10") (pinfunction "NC_M10") (pintype "passive"))
    )
    (net (code "241") (name "unconnected-(U800H-NC-PadM11)") (class "Default")
      (node (ref "U800") (pin "M11") (pinfunction "NC_M11") (pintype "passive"))
    )
    (net (code "242") (name "unconnected-(U800H-NC-PadN6)") (class "Default")
      (node (ref "U800") (pin "N6") (pinfunction "NC_N6") (pintype "passive"))
    )
    (net (code "243") (name "unconnected-(U800H-NC-PadN7)") (class "Default")
      (node (ref "U800") (pin "N7") (pinfunction "NC_N7") (pintype "passive"))
    )
    (net (code "244") (name "unconnected-(U800H-NC-PadN8)") (class "Default")
      (node (ref "U800") (pin "N8") (pinfunction "NC_N8") (pintype "passive"))
    )
    (net (code "245") (name "unconnected-(U800H-NC-PadN9)") (class "Default")
      (node (ref "U800") (pin "N9") (pinfunction "NC_N9") (pintype "passive"))
    )
    (net (code "246") (name "unconnected-(U800H-NC-PadN10)") (class "Default")
      (node (ref "U800") (pin "N10") (pinfunction "NC_N10") (pintype "passive"))
    )
    (net (code "247") (name "unconnected-(U800H-NC-PadN11)") (class "Default")
      (node (ref "U800") (pin "N11") (pinfunction "NC_N11") (pintype "passive"))
    )
    (net (code "248") (name "unconnected-(U800H-NC-PadP7)") (class "Default")
      (node (ref "U800") (pin "P7") (pinfunction "NC_P7") (pintype "passive"))
    )
    (net (code "249") (name "unconnected-(U800H-NC-PadP8)") (class "Default")
      (node (ref "U800") (pin "P8") (pinfunction "NC_P8") (pintype "passive"))
    )
    (net (code "250") (name "unconnected-(U800H-NC-PadP11)") (class "Default")
      (node (ref "U800") (pin "P11") (pinfunction "NC_P11") (pintype "passive"))
    )
    (net (code "251") (name "unconnected-(U800H-NC-PadT12)") (class "Default")
      (node (ref "U800") (pin "T12") (pinfunction "NC_T12") (pintype "passive"))
    )
    (net (code "252") (name "unconnected-(U800H-NC-PadU15)") (class "Default")
      (node (ref "U800") (pin "U15") (pinfunction "NC_U15") (pintype "passive"))
    )
    (net (code "253") (name "unconnected-(U800H-NC-PadV12)") (class "Default")
      (node (ref "U800") (pin "V12") (pinfunction "NC_V12") (pintype "passive"))
    )
    (net (code "254") (name "unconnected-(U800H-NC-PadV15)") (class "Default")
      (node (ref "U800") (pin "V15") (pinfunction "NC_V15") (pintype "passive"))
    )
  )
)
